# uClouds_002.net
KiCad netlist of a schematic drawn in EAGLE
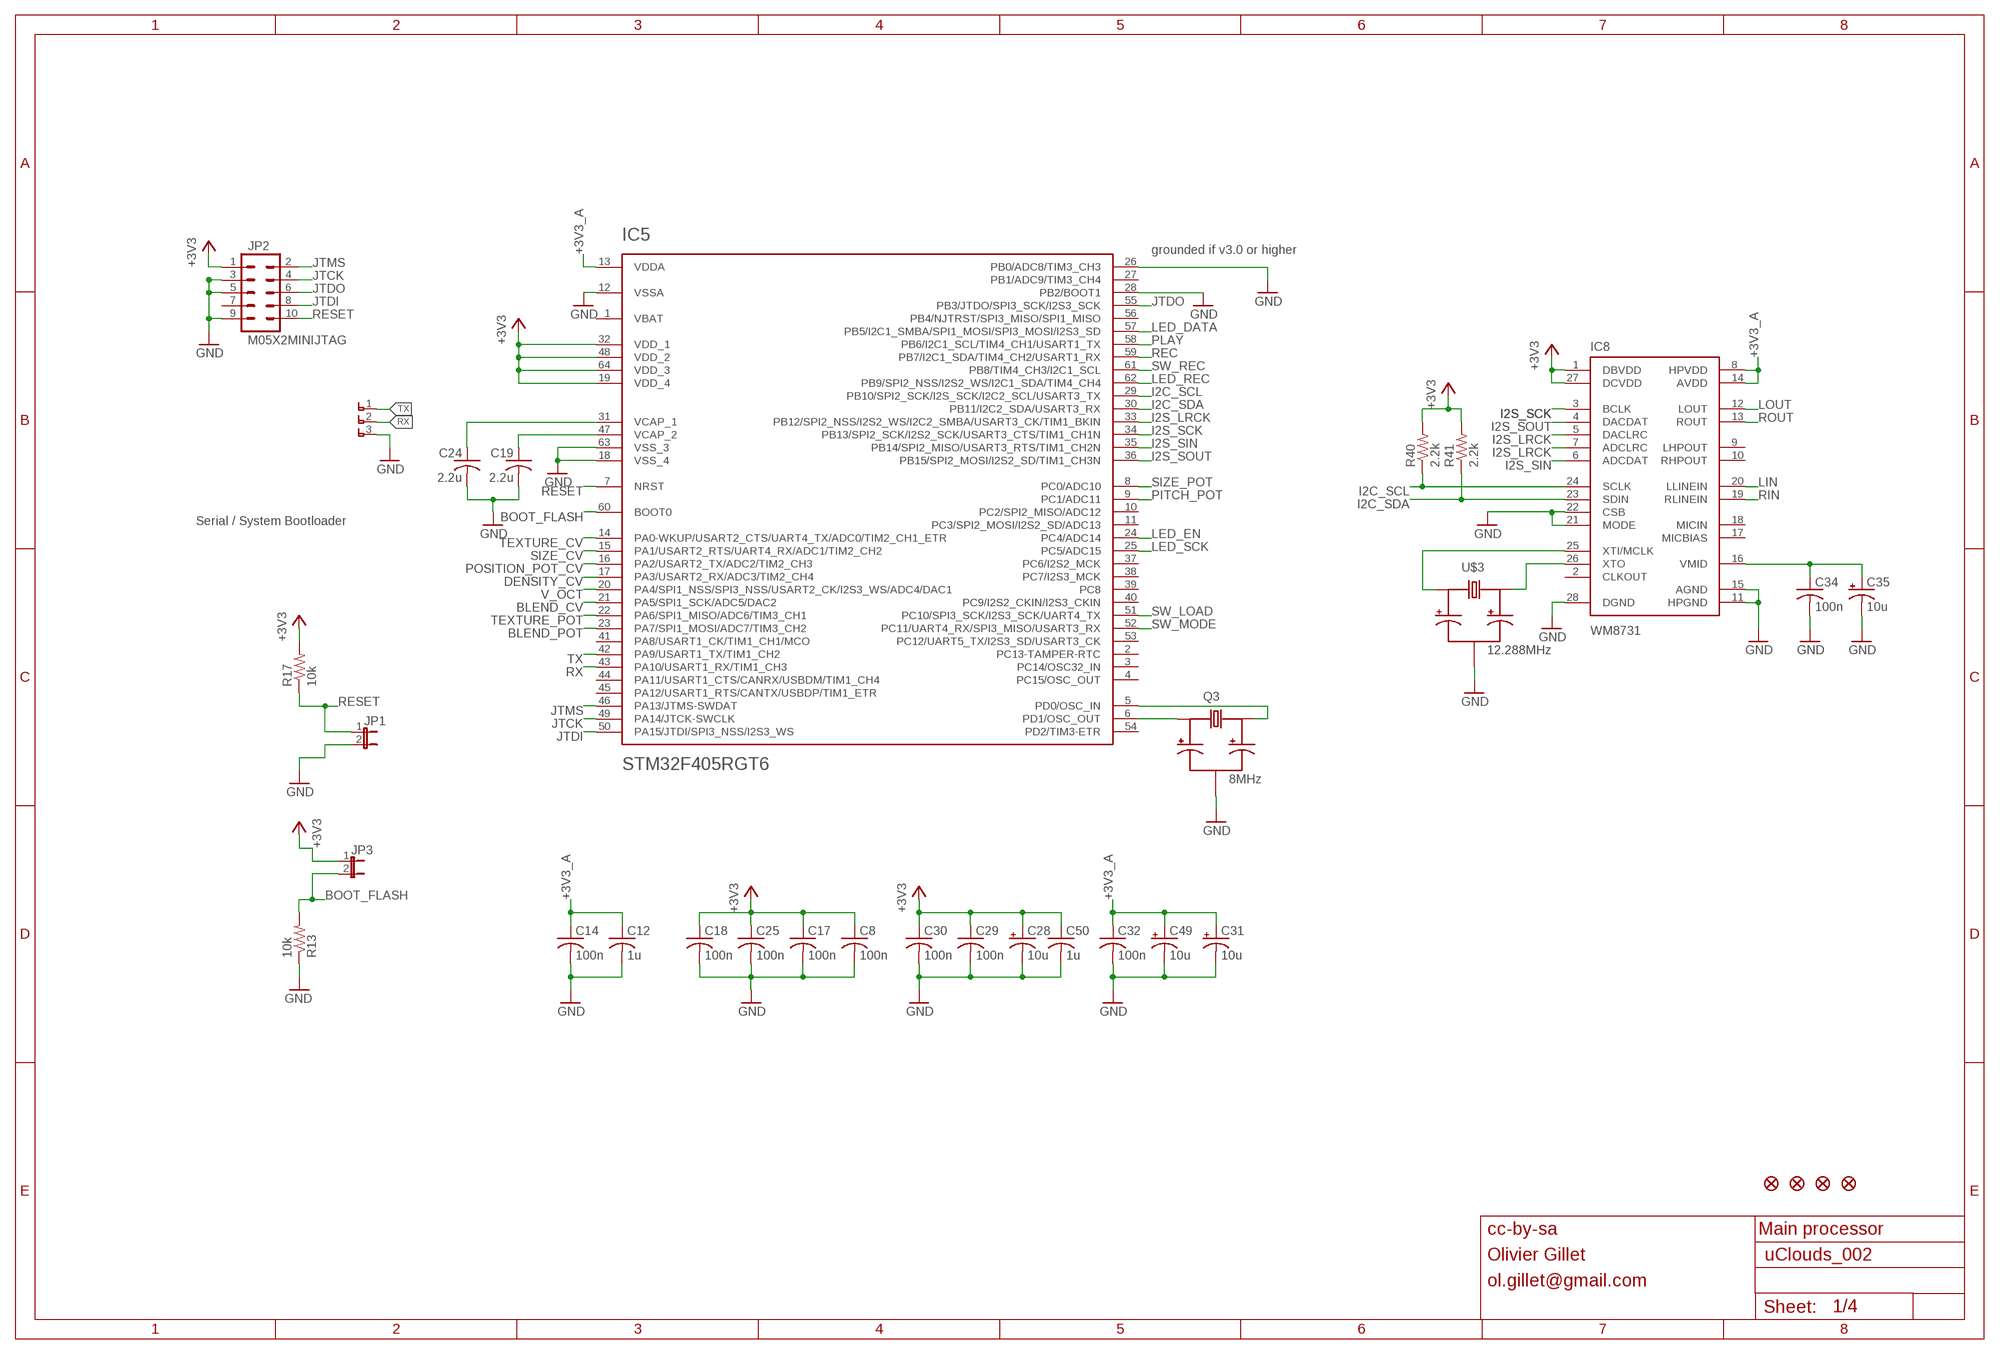
[diagram p0: schematic, sheet 1]
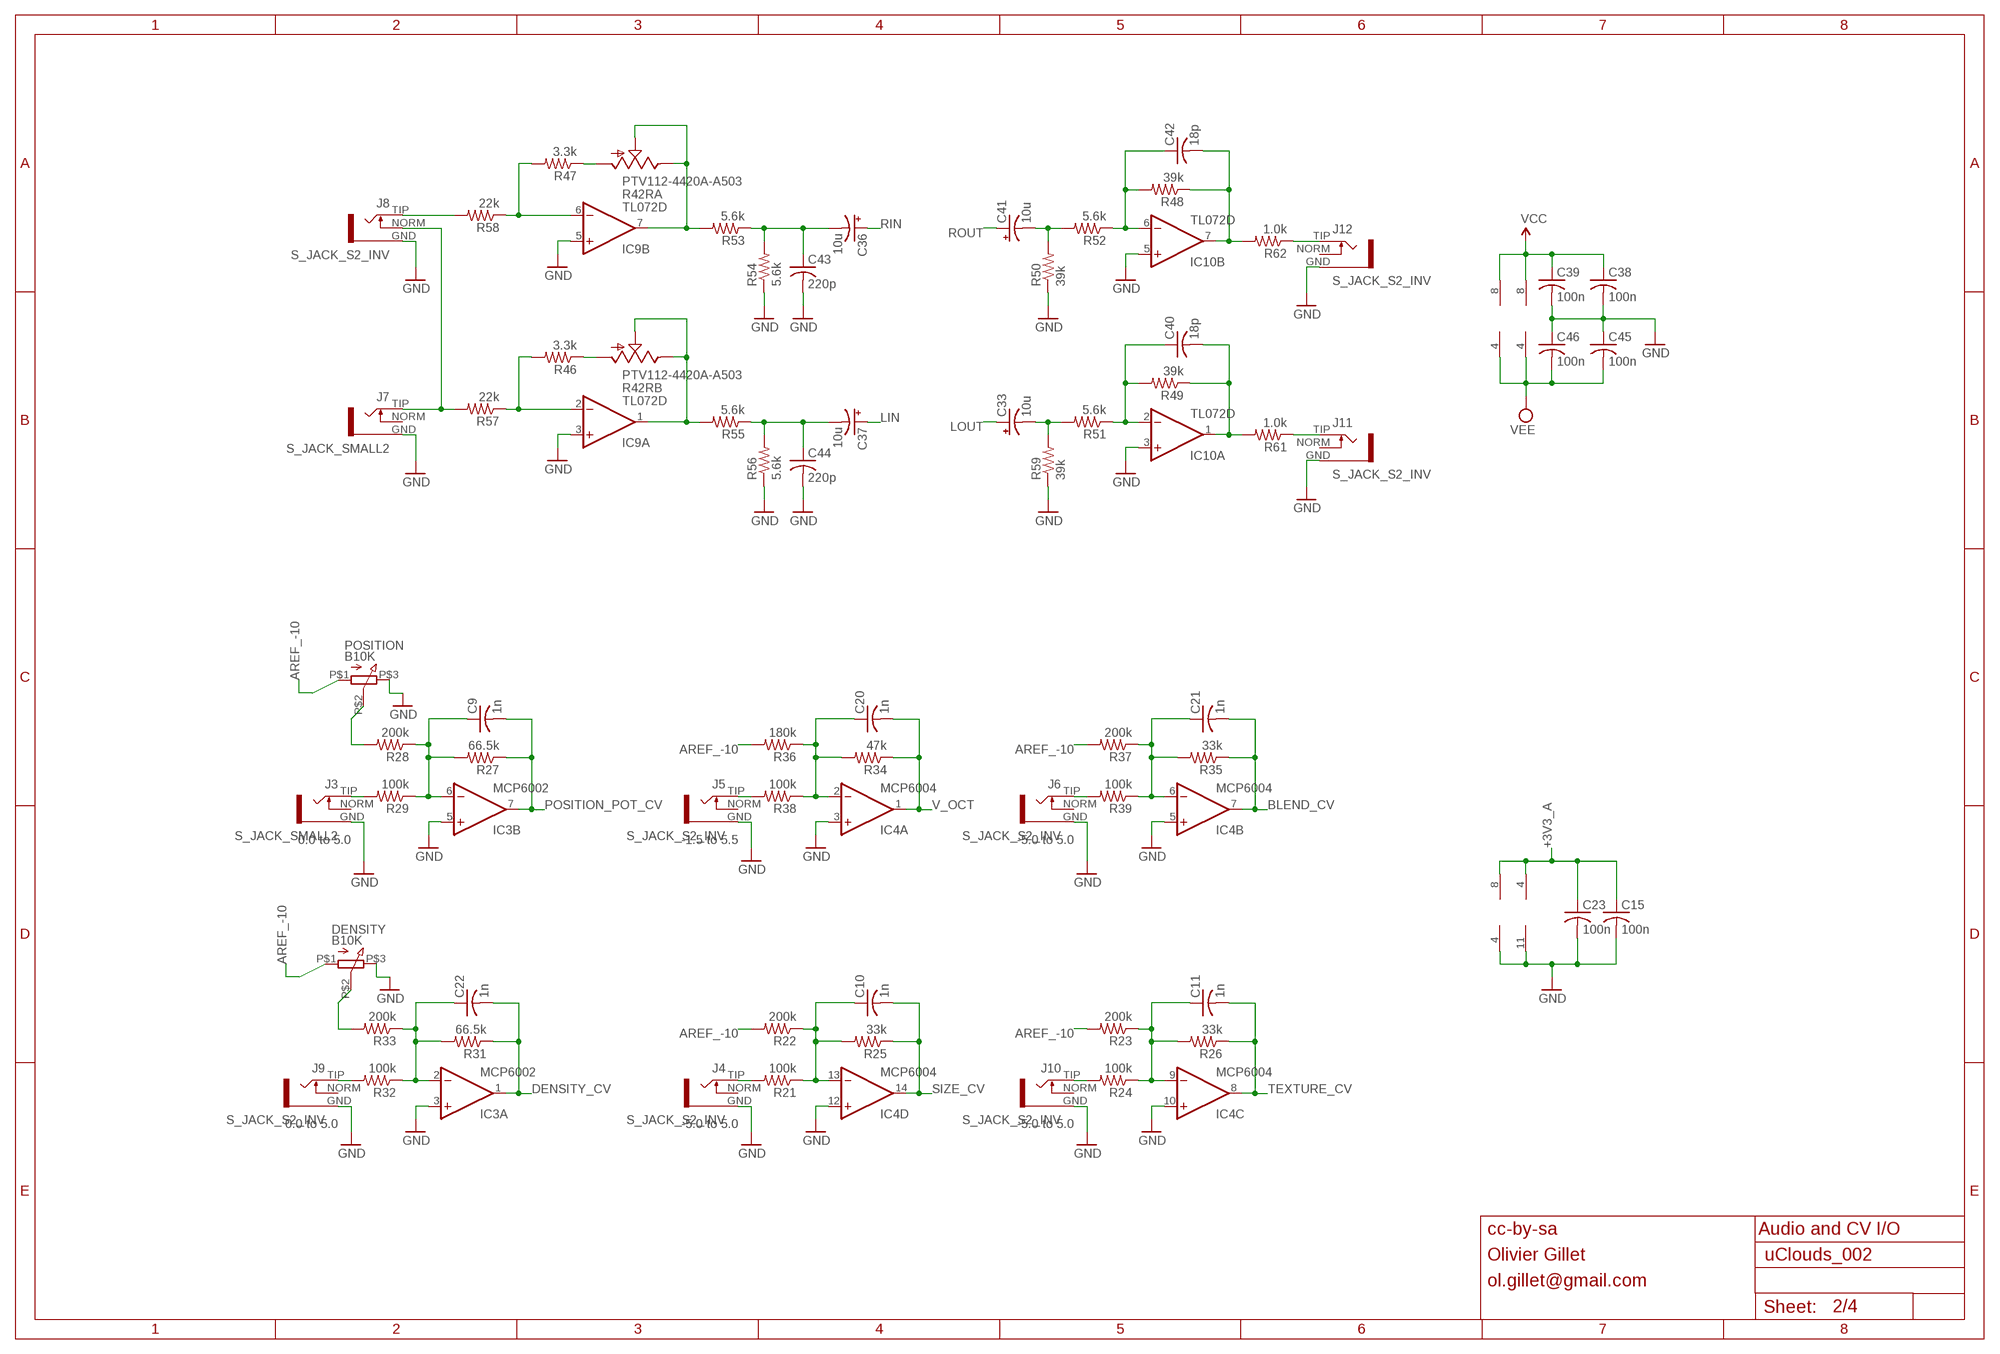
[diagram p1: schematic, sheet 2]
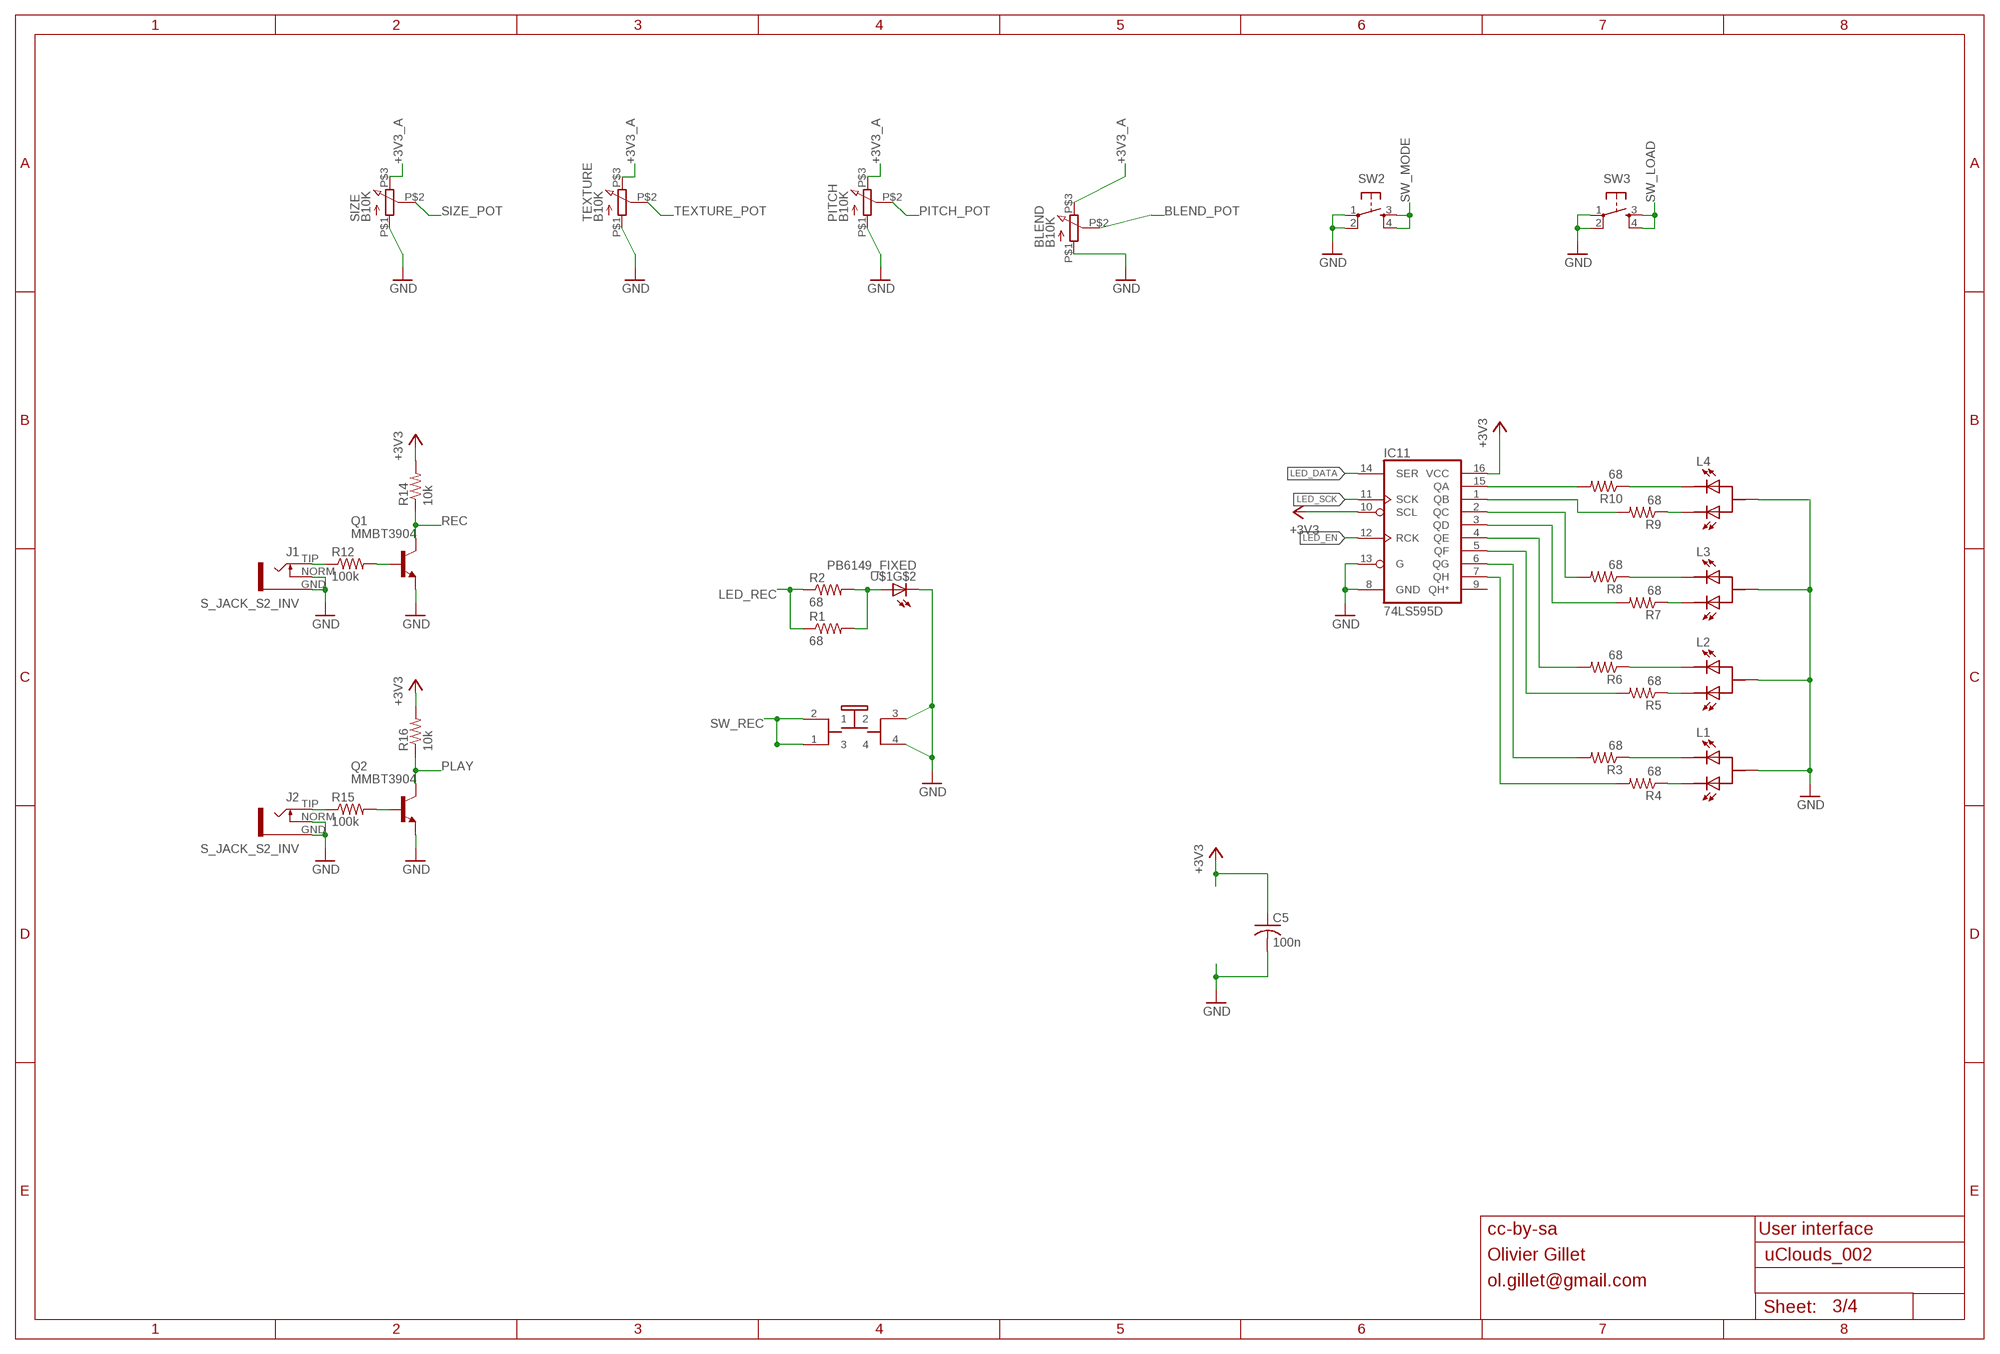
[diagram p2: schematic, sheet 3]
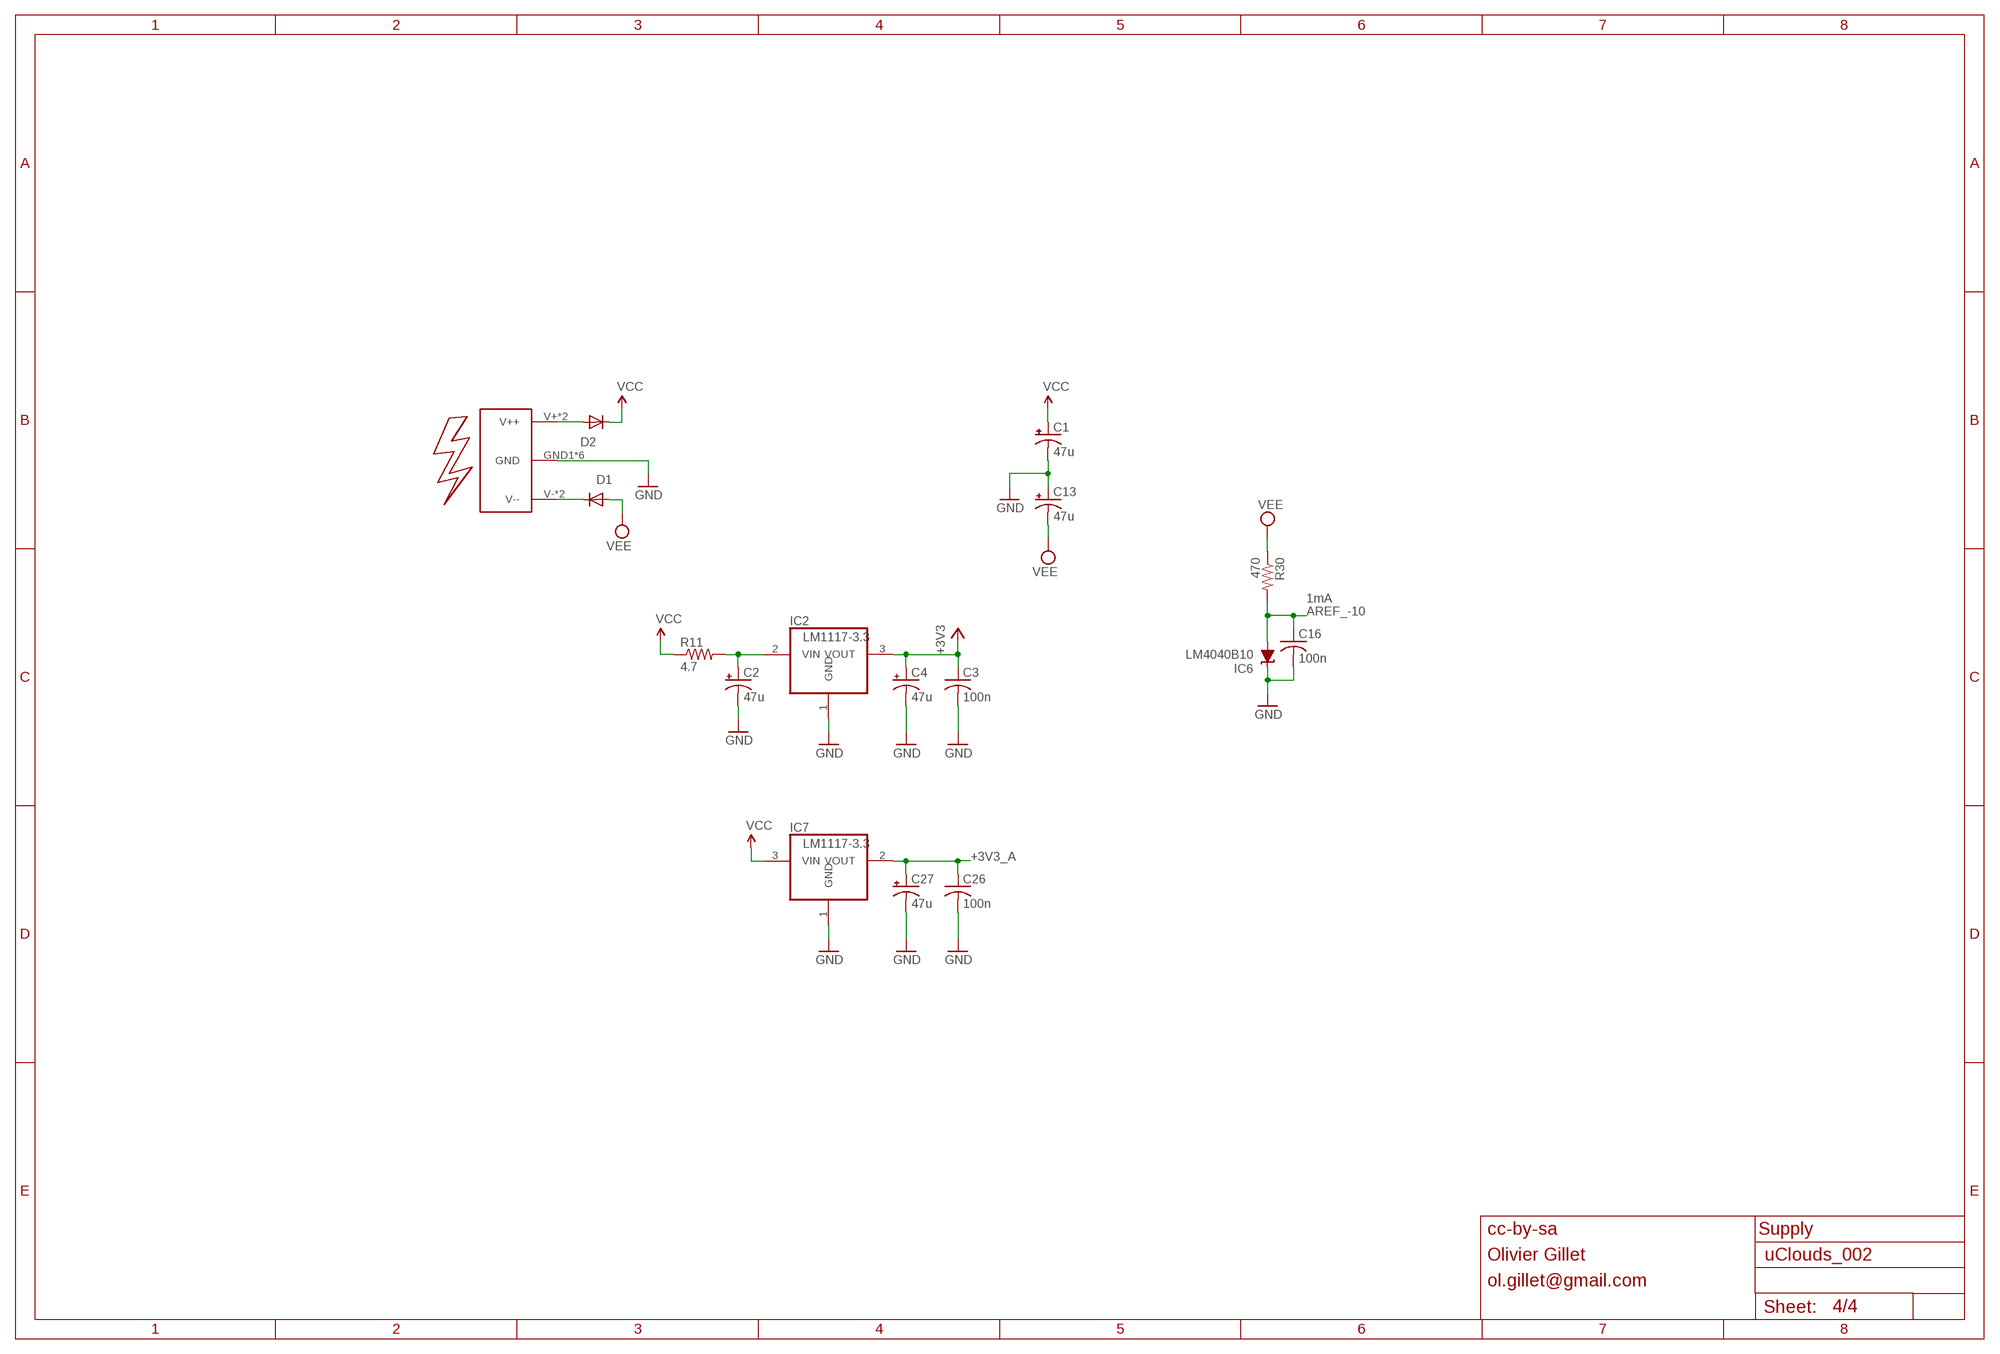
[diagram p3: schematic, sheet 4]

(export (version "E")
  (design (tool "Eeschema 10.0.6"))
  (components
    (comp (ref "C9")
      (value "1n")
      (footprint "eagle-import:C0603")
      (libsource (lib "eagle-import") (part "C-USC0603"))
    )
    (comp (ref "C10")
      (value "1n")
      (footprint "eagle-import:C0603")
      (libsource (lib "eagle-import") (part "C-USC0603"))
    )
    (comp (ref "C11")
      (value "1n")
      (footprint "eagle-import:C0603")
      (libsource (lib "eagle-import") (part "C-USC0603"))
    )
    (comp (ref "C15")
      (value "100n")
      (footprint "eagle-import:C0603K")
      (libsource (lib "eagle-import") (part "rcl@1_C-USC0603K"))
    )
    (comp (ref "C20")
      (value "1n")
      (footprint "eagle-import:C0603")
      (libsource (lib "eagle-import") (part "C-USC0603"))
    )
    (comp (ref "C21")
      (value "1n")
      (footprint "eagle-import:C0603")
      (libsource (lib "eagle-import") (part "C-USC0603"))
    )
    (comp (ref "C22")
      (value "1n")
      (footprint "eagle-import:C0603")
      (libsource (lib "eagle-import") (part "C-USC0603"))
    )
    (comp (ref "C23")
      (value "100n")
      (footprint "eagle-import:C0603")
      (libsource (lib "eagle-import") (part "C-USC0603"))
    )
    (comp (ref "C33")
      (value "10u")
      (footprint "eagle-import:PANASONIC_B")
      (libsource (lib "eagle-import") (part "CPOL-USB"))
    )
    (comp (ref "C36")
      (value "10u")
      (footprint "eagle-import:PANASONIC_B")
      (libsource (lib "eagle-import") (part "CPOL-USB"))
    )
    (comp (ref "C37")
      (value "10u")
      (footprint "eagle-import:PANASONIC_B")
      (libsource (lib "eagle-import") (part "CPOL-USB"))
    )
    (comp (ref "C38")
      (value "100n")
      (footprint "eagle-import:C0603")
      (libsource (lib "eagle-import") (part "C-USC0603"))
    )
    (comp (ref "C39")
      (value "100n")
      (footprint "eagle-import:C0603K")
      (libsource (lib "eagle-import") (part "rcl@1_C-USC0603K"))
    )
    (comp (ref "C40")
      (value "18p")
      (footprint "eagle-import:C0603")
      (libsource (lib "eagle-import") (part "C-USC0603"))
    )
    (comp (ref "C41")
      (value "10u")
      (footprint "eagle-import:PANASONIC_B")
      (libsource (lib "eagle-import") (part "CPOL-USB"))
    )
    (comp (ref "C42")
      (value "18p")
      (footprint "eagle-import:C0603")
      (libsource (lib "eagle-import") (part "C-USC0603"))
    )
    (comp (ref "C43")
      (value "220p")
      (footprint "eagle-import:C0603K")
      (libsource (lib "eagle-import") (part "C-USC0603K"))
    )
    (comp (ref "C44")
      (value "220p")
      (footprint "eagle-import:C0603")
      (libsource (lib "eagle-import") (part "C-USC0603"))
    )
    (comp (ref "C45")
      (value "100n")
      (footprint "eagle-import:C0603")
      (libsource (lib "eagle-import") (part "C-USC0603"))
    )
    (comp (ref "C46")
      (value "100n")
      (footprint "eagle-import:C0603K")
      (libsource (lib "eagle-import") (part "rcl@1_C-USC0603K"))
    )
    (comp (ref "DENSITY")
      (value "B10K")
      (footprint "eagle-import:Q-POT2")
      (libsource (lib "eagle-import") (part "Q-POT2"))
    )
    (comp (ref "IC3")
      (value "MCP6002")
      (footprint "eagle-import:SO08")
      (libsource (lib "eagle-import") (part "TL072D"))
    )
    (comp (ref "IC4")
      (value "MCP6004")
      (footprint "eagle-import:SO14")
      (libsource (lib "eagle-import") (part "TL074D"))
    )
    (comp (ref "IC9")
      (value "TL072D")
      (footprint "eagle-import:SO08")
      (libsource (lib "eagle-import") (part "og-linear_TL072D"))
    )
    (comp (ref "IC10")
      (value "TL072D")
      (footprint "eagle-import:SO08")
      (libsource (lib "eagle-import") (part "og-linear_TL072D"))
    )
    (comp (ref "J3")
      (value "S_JACK_SMALL2")
      (footprint "eagle-import:S_JACK_SMALL2")
      (libsource (lib "eagle-import") (part "S_JACK_SMALL2"))
    )
    (comp (ref "J4")
      (value "S_JACK_S2_INV")
      (footprint "eagle-import:S_JACK_S2_INV")
      (libsource (lib "eagle-import") (part "S_JACK_S2_INV"))
    )
    (comp (ref "J5")
      (value "S_JACK_S2_INV")
      (footprint "eagle-import:S_JACK_S2_INV")
      (libsource (lib "eagle-import") (part "S_JACK_S2_INV"))
    )
    (comp (ref "J6")
      (value "S_JACK_S2_INV")
      (footprint "eagle-import:S_JACK_S2_INV")
      (libsource (lib "eagle-import") (part "S_JACK_S2_INV"))
    )
    (comp (ref "J7")
      (value "S_JACK_SMALL2")
      (footprint "eagle-import:S_JACK_SMALL2")
      (libsource (lib "eagle-import") (part "S_JACK_SMALL2"))
    )
    (comp (ref "J8")
      (value "S_JACK_S2_INV")
      (footprint "eagle-import:S_JACK_S2_INV")
      (libsource (lib "eagle-import") (part "S_JACK_S2_INV"))
    )
    (comp (ref "J9")
      (value "S_JACK_S2_INV")
      (footprint "eagle-import:S_JACK_S2_INV")
      (libsource (lib "eagle-import") (part "S_JACK_S2_INV"))
    )
    (comp (ref "J10")
      (value "S_JACK_S2_INV")
      (footprint "eagle-import:S_JACK_S2_INV")
      (libsource (lib "eagle-import") (part "S_JACK_S2_INV"))
    )
    (comp (ref "J11")
      (value "S_JACK_S2_INV")
      (footprint "eagle-import:S_JACK_S2_INV")
      (libsource (lib "eagle-import") (part "S_JACK_S2_INV"))
    )
    (comp (ref "J12")
      (value "S_JACK_S2_INV")
      (footprint "eagle-import:S_JACK_S2_INV")
      (libsource (lib "eagle-import") (part "S_JACK_S2_INV"))
    )
    (comp (ref "POSITION")
      (value "B10K")
      (footprint "eagle-import:Q-POT2")
      (libsource (lib "eagle-import") (part "Q-POT2"))
    )
    (comp (ref "R21")
      (value "100k")
      (footprint "eagle-import:R0603")
      (libsource (lib "eagle-import") (part "R-US_R0603"))
    )
    (comp (ref "R22")
      (value "200k")
      (footprint "eagle-import:R0603")
      (libsource (lib "eagle-import") (part "R-US_R0603"))
    )
    (comp (ref "R23")
      (value "200k")
      (footprint "eagle-import:R0603")
      (libsource (lib "eagle-import") (part "R-US_R0603"))
    )
    (comp (ref "R24")
      (value "100k")
      (footprint "eagle-import:R0603")
      (libsource (lib "eagle-import") (part "R-US_R0603"))
    )
    (comp (ref "R25")
      (value "33k")
      (footprint "eagle-import:R0603")
      (libsource (lib "eagle-import") (part "R-US_R0603"))
    )
    (comp (ref "R26")
      (value "33k")
      (footprint "eagle-import:R0603")
      (libsource (lib "eagle-import") (part "R-US_R0603"))
    )
    (comp (ref "R27")
      (value "66.5k")
      (footprint "eagle-import:R0603")
      (libsource (lib "eagle-import") (part "R-US_R0603"))
    )
    (comp (ref "R28")
      (value "200k")
      (footprint "eagle-import:R0603")
      (libsource (lib "eagle-import") (part "R-US_R0603"))
    )
    (comp (ref "R29")
      (value "100k")
      (footprint "eagle-import:R0603")
      (libsource (lib "eagle-import") (part "R-US_R0603"))
    )
    (comp (ref "R31")
      (value "66.5k")
      (footprint "eagle-import:R0603")
      (libsource (lib "eagle-import") (part "R-US_R0603"))
    )
    (comp (ref "R32")
      (value "100k")
      (footprint "eagle-import:R0603")
      (libsource (lib "eagle-import") (part "R-US_R0603"))
    )
    (comp (ref "R33")
      (value "200k")
      (footprint "eagle-import:R0603")
      (libsource (lib "eagle-import") (part "R-US_R0603"))
    )
    (comp (ref "R34")
      (value "47k")
      (footprint "eagle-import:R0603")
      (libsource (lib "eagle-import") (part "R-US_R0603"))
    )
    (comp (ref "R35")
      (value "33k")
      (footprint "eagle-import:R0603")
      (libsource (lib "eagle-import") (part "R-US_R0603"))
    )
    (comp (ref "R36")
      (value "180k")
      (footprint "eagle-import:R0603")
      (libsource (lib "eagle-import") (part "R-US_R0603"))
    )
    (comp (ref "R37")
      (value "200k")
      (footprint "eagle-import:R0603")
      (libsource (lib "eagle-import") (part "R-US_R0603"))
    )
    (comp (ref "R38")
      (value "100k")
      (footprint "eagle-import:R0603")
      (libsource (lib "eagle-import") (part "R-US_R0603"))
    )
    (comp (ref "R39")
      (value "100k")
      (footprint "eagle-import:R0603")
      (libsource (lib "eagle-import") (part "R-US_R0603"))
    )
    (comp (ref "R42")
      (value "PTV112-4420A-A503")
      (footprint "eagle-import:BOURNS_PTV112")
      (libsource (lib "eagle-import") (part "POT_US_DUAL_GANG"))
    )
    (comp (ref "R46")
      (value "3.3k")
      (footprint "eagle-import:R0603")
      (libsource (lib "eagle-import") (part "R-US_R0603"))
    )
    (comp (ref "R47")
      (value "3.3k")
      (footprint "eagle-import:R0603")
      (libsource (lib "eagle-import") (part "R-US_R0603"))
    )
    (comp (ref "R48")
      (value "39k")
      (footprint "eagle-import:R0603")
      (libsource (lib "eagle-import") (part "R-US_R0603"))
    )
    (comp (ref "R49")
      (value "39k")
      (footprint "eagle-import:R0603")
      (libsource (lib "eagle-import") (part "R-US_R0603"))
    )
    (comp (ref "R50")
      (value "39k")
      (footprint "eagle-import:R0603")
      (libsource (lib "eagle-import") (part "R-US_R0603"))
    )
    (comp (ref "R51")
      (value "5.6k")
      (footprint "eagle-import:R0603")
      (libsource (lib "eagle-import") (part "R-US_R0603"))
    )
    (comp (ref "R52")
      (value "5.6k")
      (footprint "eagle-import:R0603")
      (libsource (lib "eagle-import") (part "R-US_R0603"))
    )
    (comp (ref "R53")
      (value "5.6k")
      (footprint "eagle-import:R0603")
      (libsource (lib "eagle-import") (part "R-US_R0603"))
    )
    (comp (ref "R54")
      (value "5.6k")
      (footprint "eagle-import:R0603")
      (libsource (lib "eagle-import") (part "R-US_R0603"))
    )
    (comp (ref "R55")
      (value "5.6k")
      (footprint "eagle-import:R0603")
      (libsource (lib "eagle-import") (part "R-US_R0603"))
    )
    (comp (ref "R56")
      (value "5.6k")
      (footprint "eagle-import:R0603")
      (libsource (lib "eagle-import") (part "R-US_R0603"))
    )
    (comp (ref "R57")
      (value "22k")
      (footprint "eagle-import:R0603")
      (libsource (lib "eagle-import") (part "R-US_R0603"))
    )
    (comp (ref "R58")
      (value "22k")
      (footprint "eagle-import:R0603")
      (libsource (lib "eagle-import") (part "R-US_R0603"))
    )
    (comp (ref "R59")
      (value "39k")
      (footprint "eagle-import:R0603")
      (libsource (lib "eagle-import") (part "R-US_R0603"))
    )
    (comp (ref "R61")
      (value "1.0k")
      (footprint "eagle-import:R0603")
      (libsource (lib "eagle-import") (part "R-US_R0603"))
    )
    (comp (ref "R62")
      (value "1.0k")
      (footprint "eagle-import:R0603")
      (libsource (lib "eagle-import") (part "R-US_R0603"))
    )
    (comp (ref "C1")
      (value "47u")
      (footprint "eagle-import:153CLV-0505")
      (libsource (lib "eagle-import") (part "CPOL-US153CLV-0505"))
    )
    (comp (ref "C2")
      (value "47u")
      (footprint "eagle-import:153CLV-0505")
      (libsource (lib "eagle-import") (part "rcl@1_CPOL-US153CLV-0505"))
    )
    (comp (ref "C3")
      (value "100n")
      (footprint "eagle-import:C0603")
      (libsource (lib "eagle-import") (part "C-USC0603"))
    )
    (comp (ref "C4")
      (value "47u")
      (footprint "eagle-import:153CLV-0505")
      (libsource (lib "eagle-import") (part "CPOL-US153CLV-0505"))
    )
    (comp (ref "C13")
      (value "47u")
      (footprint "eagle-import:153CLV-0505")
      (libsource (lib "eagle-import") (part "CPOL-US153CLV-0505"))
    )
    (comp (ref "C16")
      (value "100n")
      (footprint "eagle-import:C0603")
      (libsource (lib "eagle-import") (part "C-USC0603"))
    )
    (comp (ref "C26")
      (value "100n")
      (footprint "eagle-import:C0603")
      (libsource (lib "eagle-import") (part "C-USC0603"))
    )
    (comp (ref "C27")
      (value "47u")
      (footprint "eagle-import:153CLV-0505")
      (libsource (lib "eagle-import") (part "CPOL-US153CLV-0505"))
    )
    (comp (ref "D1")
      (value "1N5819HW")
      (footprint "eagle-import:SOD123")
      (libsource (lib "eagle-import") (part "DIODE-SOD123"))
    )
    (comp (ref "D2")
      (value "1N5819HW")
      (footprint "eagle-import:SOD123")
      (libsource (lib "eagle-import") (part "DIODE-SOD123"))
    )
    (comp (ref "IC2")
      (value "LM1117-3.3")
      (footprint "eagle-import:TO252")
      (libsource (lib "eagle-import") (part "REG1117T"))
    )
    (comp (ref "IC6")
      (value "LM4040B10")
      (footprint "eagle-import:DBZ_R-PDSO-G3")
      (libsource (lib "eagle-import") (part "LM4041DBZB12"))
    )
    (comp (ref "IC7")
      (value "LM1117-3.3")
      (footprint "eagle-import:SOT223")
      (libsource (lib "eagle-import") (part "REG1117"))
    )
    (comp (ref "R11")
      (value "4.7")
      (footprint "eagle-import:R1206")
      (libsource (lib "eagle-import") (part "R-US_R1206"))
    )
    (comp (ref "R30")
      (value "470")
      (footprint "eagle-import:R0603")
      (libsource (lib "eagle-import") (part "R-US_R0603"))
    )
    (comp (ref "U$2")
      (value "EURO_POWER2")
      (footprint "eagle-import:EURO_POWER2")
      (libsource (lib "eagle-import") (part "EURO_POWER2"))
    )
    (comp (ref "C8")
      (value "100n")
      (footprint "eagle-import:C0603")
      (libsource (lib "eagle-import") (part "C-USC0603"))
    )
    (comp (ref "C12")
      (value "1u")
      (footprint "eagle-import:C0603K")
      (libsource (lib "eagle-import") (part "C-USC0603K"))
    )
    (comp (ref "C14")
      (value "100n")
      (footprint "eagle-import:C0603K")
      (libsource (lib "eagle-import") (part "C-USC0603K"))
    )
    (comp (ref "C17")
      (value "100n")
      (footprint "eagle-import:C0603K")
      (libsource (lib "eagle-import") (part "C-USC0603K"))
    )
    (comp (ref "C18")
      (value "100n")
      (footprint "eagle-import:C0603K")
      (libsource (lib "eagle-import") (part "C-USC0603K"))
    )
    (comp (ref "C19")
      (value "2.2u")
      (footprint "eagle-import:C0805K")
      (libsource (lib "eagle-import") (part "rcl@1_C-USC0805K"))
    )
    (comp (ref "C24")
      (value "2.2u")
      (footprint "eagle-import:C0805K")
      (libsource (lib "eagle-import") (part "rcl@1_C-USC0805K"))
    )
    (comp (ref "C25")
      (value "100n")
      (footprint "eagle-import:C0603K")
      (libsource (lib "eagle-import") (part "rcl@1_C-USC0603K"))
    )
    (comp (ref "C28")
      (value "10u")
      (footprint "eagle-import:153CLV-0405")
      (libsource (lib "eagle-import") (part "rcl@1_CPOL-US153CLV-0405"))
    )
    (comp (ref "C29")
      (value "100n")
      (footprint "eagle-import:C0603K")
      (libsource (lib "eagle-import") (part "C-USC0603K"))
    )
    (comp (ref "C30")
      (value "100n")
      (footprint "eagle-import:C0603K")
      (libsource (lib "eagle-import") (part "rcl@1_C-USC0603K"))
    )
    (comp (ref "C31")
      (value "10u")
      (footprint "eagle-import:PANASONIC_B")
      (libsource (lib "eagle-import") (part "CPOL-USB"))
    )
    (comp (ref "C32")
      (value "100n")
      (footprint "eagle-import:C0603")
      (libsource (lib "eagle-import") (part "C-USC0603"))
    )
    (comp (ref "C34")
      (value "100n")
      (footprint "eagle-import:C0603")
      (libsource (lib "eagle-import") (part "C-USC0603"))
    )
    (comp (ref "C35")
      (value "10u")
      (footprint "eagle-import:PANASONIC_B")
      (libsource (lib "eagle-import") (part "CPOL-USB"))
    )
    (comp (ref "C49")
      (value "10u")
      (footprint "eagle-import:PANASONIC_A")
      (libsource (lib "eagle-import") (part "CPOL-USA"))
    )
    (comp (ref "C50")
      (value "1u")
      (footprint "eagle-import:C0603K")
      (libsource (lib "eagle-import") (part "rcl@1_C-USC0603K"))
    )
    (comp (ref "F1")
      (value "FIDUCIAL1X2")
      (footprint "eagle-import:FIDUCIAL-1X2")
      (libsource (lib "eagle-import") (part "FIDUCIAL1X2"))
    )
    (comp (ref "F2")
      (value "FIDUCIAL1X2")
      (footprint "eagle-import:FIDUCIAL-1X2")
      (libsource (lib "eagle-import") (part "FIDUCIAL1X2"))
    )
    (comp (ref "F3")
      (value "FIDUCIAL1X2")
      (footprint "eagle-import:FIDUCIAL-1X2")
      (libsource (lib "eagle-import") (part "FIDUCIAL1X2"))
    )
    (comp (ref "F4")
      (value "FIDUCIAL1X2")
      (footprint "eagle-import:FIDUCIAL-1X2")
      (libsource (lib "eagle-import") (part "FIDUCIAL1X2"))
    )
    (comp (ref "IC5")
      (value "STM32F405RGT6")
      (footprint "eagle-import:TQFP-10X10-64")
      (libsource (lib "eagle-import") (part "STM32F20X"))
    )
    (comp (ref "IC8")
      (value "WM8731")
      (footprint "eagle-import:SSOP28")
      (libsource (lib "eagle-import") (part "WM8731"))
    )
    (comp (ref "JP1")
      (value "JUMPER-2SMD-NO")
      (footprint "eagle-import:SJ_2S-NO")
      (libsource (lib "eagle-import") (part "JUMPER-2SMD-NO"))
    )
    (comp (ref "JP2")
      (value "M05X2MINIJTAG")
      (footprint "eagle-import:2X5-1.27")
      (libsource (lib "eagle-import") (part "M05X2MINIJTAG"))
    )
    (comp (ref "JP3")
      (value "JUMPER-2SMD-NO")
      (footprint "eagle-import:SJ_2S-NO")
      (libsource (lib "eagle-import") (part "JUMPER-2SMD-NO"))
    )
    (comp (ref "Q3")
      (value "8MHz")
      (footprint "eagle-import:CRYSTAL_SMALLER")
      (libsource (lib "eagle-import") (part "CRYSTAL_SMALLER"))
    )
    (comp (ref "R13")
      (value "10k")
      (footprint "eagle-import:R0603")
      (libsource (lib "eagle-import") (part "R-US_R0603"))
    )
    (comp (ref "R17")
      (value "10k")
      (footprint "eagle-import:R0603")
      (libsource (lib "eagle-import") (part "R-US_R0603"))
    )
    (comp (ref "R40")
      (value "2.2k")
      (footprint "eagle-import:R0603")
      (libsource (lib "eagle-import") (part "R-US_R0603"))
    )
    (comp (ref "R41")
      (value "2.2k")
      (footprint "eagle-import:R0603")
      (libsource (lib "eagle-import") (part "R-US_R0603"))
    )
    (comp (ref "U$3")
      (value "12.288MHz")
      (footprint "eagle-import:CRYSTAL_SMALLER")
      (libsource (lib "eagle-import") (part "CRYSTAL_SMALLER"))
    )
    (comp (ref "U$4")
      (value "1X3_SMALL")
      (footprint "eagle-import:1X3_SMALL")
      (libsource (lib "eagle-import") (part "1X3_SMALL"))
    )
    (comp (ref "BLEND")
      (value "B10K")
      (footprint "eagle-import:Q-POT2")
      (libsource (lib "eagle-import") (part "Q-POT2"))
    )
    (comp (ref "C5")
      (value "100n")
      (footprint "eagle-import:C0603")
      (libsource (lib "eagle-import") (part "C-USC0603"))
    )
    (comp (ref "IC11")
      (value "74LS595D")
      (footprint "eagle-import:SO16")
      (libsource (lib "eagle-import") (part "74595DLS"))
    )
    (comp (ref "J1")
      (value "S_JACK_S2_INV")
      (footprint "eagle-import:S_JACK_S2_INV")
      (libsource (lib "eagle-import") (part "S_JACK_S2_INV"))
    )
    (comp (ref "J2")
      (value "S_JACK_S2_INV")
      (footprint "eagle-import:S_JACK_S2_INV")
      (libsource (lib "eagle-import") (part "S_JACK_S2_INV"))
    )
    (comp (ref "L1")
      (value "LED_3MM_3PIN")
      (footprint "eagle-import:LED_3MM_3PIN")
      (libsource (lib "eagle-import") (part "LED_3MM_3PIN"))
    )
    (comp (ref "L2")
      (value "LED_3MM_3PIN")
      (footprint "eagle-import:LED_3MM_3PIN")
      (libsource (lib "eagle-import") (part "LED_3MM_3PIN"))
    )
    (comp (ref "L3")
      (value "LED_3MM_3PIN")
      (footprint "eagle-import:LED_3MM_3PIN")
      (libsource (lib "eagle-import") (part "LED_3MM_3PIN"))
    )
    (comp (ref "L4")
      (value "LED_3MM_3PIN")
      (footprint "eagle-import:LED_3MM_3PIN")
      (libsource (lib "eagle-import") (part "LED_3MM_3PIN"))
    )
    (comp (ref "PITCH")
      (value "B10K")
      (footprint "eagle-import:Q-POT2")
      (libsource (lib "eagle-import") (part "Q-POT2"))
    )
    (comp (ref "Q1")
      (value "MMBT3904")
      (footprint "eagle-import:SOT23-BEC")
      (libsource (lib "eagle-import") (part "-NPN-SOT23-BECMMBT3904LT1"))
    )
    (comp (ref "Q2")
      (value "MMBT3904")
      (footprint "eagle-import:SOT23-BEC")
      (libsource (lib "eagle-import") (part "-NPN-SOT23-BECMMBT3904LT1"))
    )
    (comp (ref "R1")
      (value "68")
      (footprint "eagle-import:R0603")
      (libsource (lib "eagle-import") (part "R-US_R0603"))
    )
    (comp (ref "R2")
      (value "68")
      (footprint "eagle-import:R0603")
      (libsource (lib "eagle-import") (part "R-US_R0603"))
    )
    (comp (ref "R3")
      (value "68")
      (footprint "eagle-import:R0603")
      (libsource (lib "eagle-import") (part "R-US_R0603"))
    )
    (comp (ref "R4")
      (value "68")
      (footprint "eagle-import:R0603")
      (libsource (lib "eagle-import") (part "R-US_R0603"))
    )
    (comp (ref "R5")
      (value "68")
      (footprint "eagle-import:R0603")
      (libsource (lib "eagle-import") (part "R-US_R0603"))
    )
    (comp (ref "R6")
      (value "68")
      (footprint "eagle-import:R0603")
      (libsource (lib "eagle-import") (part "R-US_R0603"))
    )
    (comp (ref "R7")
      (value "68")
      (footprint "eagle-import:R0603")
      (libsource (lib "eagle-import") (part "R-US_R0603"))
    )
    (comp (ref "R8")
      (value "68")
      (footprint "eagle-import:R0603")
      (libsource (lib "eagle-import") (part "R-US_R0603"))
    )
    (comp (ref "R9")
      (value "68")
      (footprint "eagle-import:R0603")
      (libsource (lib "eagle-import") (part "R-US_R0603"))
    )
    (comp (ref "R10")
      (value "68")
      (footprint "eagle-import:R0603")
      (libsource (lib "eagle-import") (part "R-US_R0603"))
    )
    (comp (ref "R12")
      (value "100k")
      (footprint "eagle-import:R0603")
      (libsource (lib "eagle-import") (part "R-US_R0603"))
    )
    (comp (ref "R14")
      (value "10k")
      (footprint "eagle-import:R0603")
      (libsource (lib "eagle-import") (part "R-US_R0603"))
    )
    (comp (ref "R15")
      (value "100k")
      (footprint "eagle-import:R0603")
      (libsource (lib "eagle-import") (part "R-US_R0603"))
    )
    (comp (ref "R16")
      (value "10k")
      (footprint "eagle-import:R0603")
      (libsource (lib "eagle-import") (part "R-US_R0603"))
    )
    (comp (ref "SIZE")
      (value "B10K")
      (footprint "eagle-import:Q-POT2")
      (libsource (lib "eagle-import") (part "Q-POT2"))
    )
    (comp (ref "SW2")
      (value "TAC_SWITCHPTH")
      (footprint "eagle-import:TACTILE-PTH")
      (libsource (lib "eagle-import") (part "TAC_SWITCHPTH"))
    )
    (comp (ref "SW3")
      (value "TAC_SWITCHPTH")
      (footprint "eagle-import:TACTILE-PTH")
      (libsource (lib "eagle-import") (part "TAC_SWITCHPTH"))
    )
    (comp (ref "TEXTURE")
      (value "B10K")
      (footprint "eagle-import:Q-POT2")
      (libsource (lib "eagle-import") (part "Q-POT2"))
    )
    (comp (ref "U$1")
      (value "PB6149_FIXED")
      (footprint "eagle-import:PB6149L")
      (libsource (lib "eagle-import") (part "PB6149_FIXED"))
    )
  )
  (nets
    (net (code "1") (name "+3V3") (class "Default")
      (node (ref "C17") (pin "1") (pinfunction "1_1") (pintype "passive"))
      (node (ref "C18") (pin "1") (pinfunction "1_1") (pintype "passive"))
      (node (ref "C25") (pin "1") (pinfunction "1_1") (pintype "passive"))
      (node (ref "C28") (pin "+") (pinfunction "+_+") (pintype "passive"))
      (node (ref "C29") (pin "1") (pinfunction "1_1") (pintype "passive"))
      (node (ref "C3") (pin "1") (pinfunction "1_1") (pintype "passive"))
      (node (ref "C30") (pin "1") (pinfunction "1_1") (pintype "passive"))
      (node (ref "C4") (pin "+") (pinfunction "+_+") (pintype "passive"))
      (node (ref "C5") (pin "1") (pinfunction "1_1") (pintype "passive"))
      (node (ref "C50") (pin "1") (pinfunction "1_1") (pintype "passive"))
      (node (ref "C8") (pin "1") (pinfunction "1_1") (pintype "passive"))
      (node (ref "IC11") (pin "10") (pinfunction "SCL_10") (pintype "input"))
      (node (ref "IC11") (pin "16") (pinfunction "VCC_16") (pintype "power_in"))
      (node (ref "IC2") (pin "3") (pinfunction "VOUT_3") (pintype "output"))
      (node (ref "IC5") (pin "19") (pinfunction "VDD_4_19") (pintype "power_in"))
      (node (ref "IC5") (pin "32") (pinfunction "VDD_1_32") (pintype "power_in"))
      (node (ref "IC5") (pin "48") (pinfunction "VDD_2_48") (pintype "power_in"))
      (node (ref "IC5") (pin "64") (pinfunction "VDD_3_64") (pintype "power_in"))
      (node (ref "IC8") (pin "1") (pinfunction "DBVDD_1") (pintype "bidirectional"))
      (node (ref "IC8") (pin "27") (pinfunction "DCVDD_27") (pintype "bidirectional"))
      (node (ref "JP2") (pin "1") (pinfunction "1_1") (pintype "passive"))
      (node (ref "JP3") (pin "1") (pinfunction "1_1") (pintype "passive"))
      (node (ref "R14") (pin "2") (pinfunction "2_2") (pintype "passive"))
      (node (ref "R16") (pin "2") (pinfunction "2_2") (pintype "passive"))
      (node (ref "R17") (pin "2") (pinfunction "2_2") (pintype "passive"))
      (node (ref "R40") (pin "2") (pinfunction "2_2") (pintype "passive"))
      (node (ref "R41") (pin "2") (pinfunction "2_2") (pintype "passive"))
    )
    (net (code "2") (name "+3V3_A") (class "Default")
      (node (ref "BLEND") (pin "P$3") (pinfunction "3_P$3") (pintype "passive"))
      (node (ref "C12") (pin "1") (pinfunction "1_1") (pintype "passive"))
      (node (ref "C14") (pin "1") (pinfunction "1_1") (pintype "passive"))
      (node (ref "C15") (pin "1") (pinfunction "1_1") (pintype "passive"))
      (node (ref "C23") (pin "1") (pinfunction "1_1") (pintype "passive"))
      (node (ref "C26") (pin "1") (pinfunction "1_1") (pintype "passive"))
      (node (ref "C27") (pin "+") (pinfunction "+_+") (pintype "passive"))
      (node (ref "C31") (pin "+") (pinfunction "+_+") (pintype "passive"))
      (node (ref "C32") (pin "1") (pinfunction "1_1") (pintype "passive"))
      (node (ref "C49") (pin "+") (pinfunction "+_+") (pintype "passive"))
      (node (ref "IC3") (pin "8") (pinfunction "V+_8") (pintype "power_in"))
      (node (ref "IC4") (pin "4") (pinfunction "V+_4") (pintype "power_in"))
      (node (ref "IC5") (pin "13") (pinfunction "VDDA_13") (pintype "power_in"))
      (node (ref "IC7") (pin "2") (pinfunction "VOUT_2") (pintype "output"))
      (node (ref "IC8") (pin "14") (pinfunction "AVDD_14") (pintype "bidirectional"))
      (node (ref "IC8") (pin "8") (pinfunction "HPVDD_8") (pintype "bidirectional"))
      (node (ref "PITCH") (pin "P$3") (pinfunction "3_P$3") (pintype "passive"))
      (node (ref "SIZE") (pin "P$3") (pinfunction "3_P$3") (pintype "passive"))
      (node (ref "TEXTURE") (pin "P$3") (pinfunction "3_P$3") (pintype "passive"))
    )
    (net (code "3") (name "AREF_-10") (class "Default")
      (node (ref "C16") (pin "1") (pinfunction "1_1") (pintype "passive"))
      (node (ref "DENSITY") (pin "P$1") (pinfunction "1_P$1") (pintype "passive"))
      (node (ref "IC6") (pin "2") (pinfunction "A_2") (pintype "passive"))
      (node (ref "POSITION") (pin "P$1") (pinfunction "1_P$1") (pintype "passive"))
      (node (ref "R22") (pin "2") (pinfunction "2_2") (pintype "passive"))
      (node (ref "R23") (pin "2") (pinfunction "2_2") (pintype "passive"))
      (node (ref "R30") (pin "2") (pinfunction "2_2") (pintype "passive"))
      (node (ref "R36") (pin "2") (pinfunction "2_2") (pintype "passive"))
      (node (ref "R37") (pin "2") (pinfunction "2_2") (pintype "passive"))
    )
    (net (code "4") (name "BLEND_CV") (class "Default")
      (node (ref "C21") (pin "2") (pinfunction "2_2") (pintype "passive"))
      (node (ref "IC4") (pin "7") (pinfunction "OUT_7") (pintype "output"))
      (node (ref "IC5") (pin "21") (pinfunction "PA5/SPI1_SCK/ADC5/DAC2_21") (pintype "bidirectional"))
      (node (ref "R35") (pin "1") (pinfunction "1_1") (pintype "passive"))
    )
    (net (code "5") (name "BLEND_POT") (class "Default")
      (node (ref "BLEND") (pin "P$2") (pinfunction "2_P$2") (pintype "passive"))
      (node (ref "IC5") (pin "23") (pinfunction "PA7/SPI1_MOSI/ADC7/TIM3_CH2_23") (pintype "bidirectional"))
    )
    (net (code "6") (name "BOOT_FLASH") (class "Default")
      (node (ref "IC5") (pin "60") (pinfunction "BOOT0_60") (pintype "bidirectional"))
      (node (ref "JP3") (pin "2") (pinfunction "2_2") (pintype "passive"))
      (node (ref "R13") (pin "2") (pinfunction "2_2") (pintype "passive"))
    )
    (net (code "7") (name "DENSITY_CV") (class "Default")
      (node (ref "C22") (pin "2") (pinfunction "2_2") (pintype "passive"))
      (node (ref "IC3") (pin "1") (pinfunction "OUT_1") (pintype "output"))
      (node (ref "IC5") (pin "17") (pinfunction "PA3/USART2_RX/ADC3/TIM2_CH4_17") (pintype "bidirectional"))
      (node (ref "R31") (pin "1") (pinfunction "1_1") (pintype "passive"))
    )
    (net (code "8") (name "GND") (class "Default")
      (node (ref "BLEND") (pin "P$1") (pinfunction "1_P$1") (pintype "passive"))
      (node (ref "C1") (pin "-") (pinfunction "-_-") (pintype "passive"))
      (node (ref "C12") (pin "2") (pinfunction "2_2") (pintype "passive"))
      (node (ref "C13") (pin "+") (pinfunction "+_+") (pintype "passive"))
      (node (ref "C14") (pin "2") (pinfunction "2_2") (pintype "passive"))
      (node (ref "C15") (pin "2") (pinfunction "2_2") (pintype "passive"))
      (node (ref "C16") (pin "2") (pinfunction "2_2") (pintype "passive"))
      (node (ref "C17") (pin "2") (pinfunction "2_2") (pintype "passive"))
      (node (ref "C18") (pin "2") (pinfunction "2_2") (pintype "passive"))
      (node (ref "C19") (pin "2") (pinfunction "2_2") (pintype "passive"))
      (node (ref "C2") (pin "-") (pinfunction "-_-") (pintype "passive"))
      (node (ref "C23") (pin "2") (pinfunction "2_2") (pintype "passive"))
      (node (ref "C24") (pin "2") (pinfunction "2_2") (pintype "passive"))
      (node (ref "C25") (pin "2") (pinfunction "2_2") (pintype "passive"))
      (node (ref "C26") (pin "2") (pinfunction "2_2") (pintype "passive"))
      (node (ref "C27") (pin "-") (pinfunction "-_-") (pintype "passive"))
      (node (ref "C28") (pin "-") (pinfunction "-_-") (pintype "passive"))
      (node (ref "C29") (pin "2") (pinfunction "2_2") (pintype "passive"))
      (node (ref "C3") (pin "2") (pinfunction "2_2") (pintype "passive"))
      (node (ref "C30") (pin "2") (pinfunction "2_2") (pintype "passive"))
      (node (ref "C31") (pin "-") (pinfunction "-_-") (pintype "passive"))
      (node (ref "C32") (pin "2") (pinfunction "2_2") (pintype "passive"))
      (node (ref "C34") (pin "2") (pinfunction "2_2") (pintype "passive"))
      (node (ref "C35") (pin "-") (pinfunction "-_-") (pintype "passive"))
      (node (ref "C38") (pin "2") (pinfunction "2_2") (pintype "passive"))
      (node (ref "C39") (pin "2") (pinfunction "2_2") (pintype "passive"))
      (node (ref "C4") (pin "-") (pinfunction "-_-") (pintype "passive"))
      (node (ref "C43") (pin "2") (pinfunction "2_2") (pintype "passive"))
      (node (ref "C44") (pin "2") (pinfunction "2_2") (pintype "passive"))
      (node (ref "C45") (pin "1") (pinfunction "1_1") (pintype "passive"))
      (node (ref "C46") (pin "1") (pinfunction "1_1") (pintype "passive"))
      (node (ref "C49") (pin "-") (pinfunction "-_-") (pintype "passive"))
      (node (ref "C5") (pin "2") (pinfunction "2_2") (pintype "passive"))
      (node (ref "C50") (pin "2") (pinfunction "2_2") (pintype "passive"))
      (node (ref "C8") (pin "2") (pinfunction "2_2") (pintype "passive"))
      (node (ref "DENSITY") (pin "P$3") (pinfunction "3_P$3") (pintype "passive"))
      (node (ref "IC10") (pin "3") (pinfunction "+IN_3") (pintype "input"))
      (node (ref "IC10") (pin "5") (pinfunction "+IN_5") (pintype "input"))
      (node (ref "IC11") (pin "13") (pinfunction "G_13") (pintype "input"))
      (node (ref "IC11") (pin "8") (pinfunction "GND_8") (pintype "power_in"))
      (node (ref "IC2") (pin "1") (pinfunction "GND_1") (pintype "power_in"))
      (node (ref "IC3") (pin "3") (pinfunction "+IN_3") (pintype "input"))
      (node (ref "IC3") (pin "4") (pinfunction "V-_4") (pintype "power_in"))
      (node (ref "IC3") (pin "5") (pinfunction "+IN_5") (pintype "input"))
      (node (ref "IC4") (pin "10") (pinfunction "+IN_10") (pintype "input"))
      (node (ref "IC4") (pin "11") (pinfunction "V-_11") (pintype "power_in"))
      (node (ref "IC4") (pin "12") (pinfunction "+IN_12") (pintype "input"))
      (node (ref "IC4") (pin "3") (pinfunction "+IN_3") (pintype "input"))
      (node (ref "IC4") (pin "5") (pinfunction "+IN_5") (pintype "input"))
      (node (ref "IC5") (pin "12") (pinfunction "VSSA_12") (pintype "power_in"))
      (node (ref "IC5") (pin "18") (pinfunction "VSS_4_18") (pintype "power_in"))
      (node (ref "IC5") (pin "26") (pinfunction "PB0/ADC8/TIM3_CH3_26") (pintype "bidirectional"))
      (node (ref "IC5") (pin "28") (pinfunction "PB2/BOOT1_28") (pintype "bidirectional"))
      (node (ref "IC5") (pin "63") (pinfunction "VSS_3_63") (pintype "power_in"))
      (node (ref "IC6") (pin "1") (pinfunction "C_1") (pintype "passive"))
      (node (ref "IC7") (pin "1") (pinfunction "GND_1") (pintype "power_in"))
      (node (ref "IC8") (pin "11") (pinfunction "HPGND_11") (pintype "bidirectional"))
      (node (ref "IC8") (pin "15") (pinfunction "AGND_15") (pintype "bidirectional"))
      (node (ref "IC8") (pin "21") (pinfunction "MODE_21") (pintype "bidirectional"))
      (node (ref "IC8") (pin "22") (pinfunction "CSB_22") (pintype "bidirectional"))
      (node (ref "IC8") (pin "28") (pinfunction "DGND_28") (pintype "bidirectional"))
      (node (ref "IC9") (pin "3") (pinfunction "+IN_3") (pintype "input"))
      (node (ref "IC9") (pin "5") (pinfunction "+IN_5") (pintype "input"))
      (node (ref "J1") (pin "GND") (pinfunction "GND_GND") (pintype "passive"))
      (node (ref "J1") (pin "NORM") (pinfunction "NORM_NORM") (pintype "passive"))
      (node (ref "J10") (pin "GND") (pinfunction "GND_GND") (pintype "passive"))
      (node (ref "J11") (pin "GND") (pinfunction "GND_GND") (pintype "passive"))
      (node (ref "J12") (pin "GND") (pinfunction "GND_GND") (pintype "passive"))
      (node (ref "J2") (pin "GND") (pinfunction "GND_GND") (pintype "passive"))
      (node (ref "J2") (pin "NORM") (pinfunction "NORM_NORM") (pintype "passive"))
      (node (ref "J3") (pin "GND") (pinfunction "GND_GND") (pintype "passive"))
      (node (ref "J4") (pin "GND") (pinfunction "GND_GND") (pintype "passive"))
      (node (ref "J5") (pin "GND") (pinfunction "GND_GND") (pintype "passive"))
      (node (ref "J6") (pin "GND") (pinfunction "GND_GND") (pintype "passive"))
      (node (ref "J7") (pin "GND") (pinfunction "GND_GND") (pintype "passive"))
      (node (ref "J8") (pin "GND") (pinfunction "GND_GND") (pintype "passive"))
      (node (ref "J9") (pin "GND") (pinfunction "GND_GND") (pintype "passive"))
      (node (ref "JP1") (pin "2") (pinfunction "2_2") (pintype "passive"))
      (node (ref "JP2") (pin "3") (pinfunction "3_3") (pintype "passive"))
      (node (ref "JP2") (pin "5") (pinfunction "5_5") (pintype "passive"))
      (node (ref "JP2") (pin "9") (pinfunction "9_9") (pintype "passive"))
      (node (ref "L1") (pin "A") (pinfunction "A_A") (pintype "passive"))
      (node (ref "L2") (pin "A") (pinfunction "A_A") (pintype "passive"))
      (node (ref "L3") (pin "A") (pinfunction "A_A") (pintype "passive"))
      (node (ref "L4") (pin "A") (pinfunction "A_A") (pintype "passive"))
      (node (ref "PITCH") (pin "P$1") (pinfunction "1_P$1") (pintype "passive"))
      (node (ref "POSITION") (pin "P$3") (pinfunction "3_P$3") (pintype "passive"))
      (node (ref "Q1") (pin "E") (pinfunction "E_E") (pintype "passive"))
      (node (ref "Q2") (pin "E") (pinfunction "E_E") (pintype "passive"))
      (node (ref "Q3") (pin "GND") (pinfunction "GND_GND") (pintype "bidirectional"))
      (node (ref "R13") (pin "1") (pinfunction "1_1") (pintype "passive"))
      (node (ref "R50") (pin "1") (pinfunction "1_1") (pintype "passive"))
      (node (ref "R54") (pin "1") (pinfunction "1_1") (pintype "passive"))
      (node (ref "R56") (pin "1") (pinfunction "1_1") (pintype "passive"))
      (node (ref "R59") (pin "1") (pinfunction "1_1") (pintype "passive"))
      (node (ref "SIZE") (pin "P$1") (pinfunction "1_P$1") (pintype "passive"))
      (node (ref "SW2") (pin "1") (pinfunction "1_1") (pintype "passive"))
      (node (ref "SW2") (pin "2") (pinfunction "2_2") (pintype "passive"))
      (node (ref "SW3") (pin "1") (pinfunction "1_1") (pintype "passive"))
      (node (ref "SW3") (pin "2") (pinfunction "2_2") (pintype "passive"))
      (node (ref "TEXTURE") (pin "P$1") (pinfunction "1_P$1") (pintype "passive"))
      (node (ref "U$1") (pin "3") (pinfunction "2_3") (pintype "bidirectional"))
      (node (ref "U$1") (pin "4") (pinfunction "4_4") (pintype "bidirectional"))
      (node (ref "U$1") (pin "K") (pinfunction "C_K") (pintype "passive"))
      (node (ref "U$2") (pin "GND1") (pinfunction "GND_GND1") (pintype "bidirectional"))
      (node (ref "U$2") (pin "GND2") (pinfunction "GND_GND2") (pintype "bidirectional"))
      (node (ref "U$2") (pin "GND3") (pinfunction "GND_GND3") (pintype "bidirectional"))
      (node (ref "U$2") (pin "GND4") (pinfunction "GND_GND4") (pintype "bidirectional"))
      (node (ref "U$2") (pin "GND5") (pinfunction "GND_GND5") (pintype "bidirectional"))
      (node (ref "U$2") (pin "GND6") (pinfunction "GND_GND6") (pintype "bidirectional"))
      (node (ref "U$3") (pin "GND") (pinfunction "GND_GND") (pintype "bidirectional"))
      (node (ref "U$4") (pin "3") (pinfunction "P$1_3") (pintype "bidirectional"))
    )
    (net (code "9") (name "I2C_SCL") (class "Default")
      (node (ref "IC5") (pin "29") (pinfunction "PB10/SPI2_SCK/I2S_SCK/I2C2_SCL/USART3_TX_29") (pintype "bidirectional"))
      (node (ref "IC8") (pin "24") (pinfunction "SCLK_24") (pintype "bidirectional"))
      (node (ref "R40") (pin "1") (pinfunction "1_1") (pintype "passive"))
    )
    (net (code "10") (name "I2C_SDA") (class "Default")
      (node (ref "IC5") (pin "30") (pinfunction "PB11/I2C2_SDA/USART3_RX_30") (pintype "bidirectional"))
      (node (ref "IC8") (pin "23") (pinfunction "SDIN_23") (pintype "bidirectional"))
      (node (ref "R41") (pin "1") (pinfunction "1_1") (pintype "passive"))
    )
    (net (code "11") (name "I2S_LRCK") (class "Default")
      (node (ref "IC5") (pin "33") (pinfunction "PB12/SPI2_NSS/I2S2_WS/I2C2_SMBA/USART3_CK/TIM1_BKIN_33") (pintype "bidirectional"))
      (node (ref "IC8") (pin "5") (pinfunction "DACLRC_5") (pintype "bidirectional"))
      (node (ref "IC8") (pin "7") (pinfunction "ADCLRC_7") (pintype "bidirectional"))
    )
    (net (code "12") (name "I2S_SCK") (class "Default")
      (node (ref "IC5") (pin "34") (pinfunction "PB13/SPI2_SCK/I2S2_SCK/USART3_CTS/TIM1_CH1N_34") (pintype "bidirectional"))
      (node (ref "IC8") (pin "3") (pinfunction "BCLK_3") (pintype "bidirectional"))
    )
    (net (code "13") (name "I2S_SIN") (class "Default")
      (node (ref "IC5") (pin "35") (pinfunction "PB14/SPI2_MISO/USART3_RTS/TIM1_CH2N_35") (pintype "bidirectional"))
      (node (ref "IC8") (pin "6") (pinfunction "ADCDAT_6") (pintype "bidirectional"))
    )
    (net (code "14") (name "I2S_SOUT") (class "Default")
      (node (ref "IC5") (pin "36") (pinfunction "PB15/SPI2_MOSI/I2S2_SD/TIM1_CH3N_36") (pintype "bidirectional"))
      (node (ref "IC8") (pin "4") (pinfunction "DACDAT_4") (pintype "bidirectional"))
    )
    (net (code "15") (name "JTCK") (class "Default")
      (node (ref "IC5") (pin "49") (pinfunction "PA14/JTCK-SWCLK_49") (pintype "bidirectional"))
      (node (ref "JP2") (pin "4") (pinfunction "4_4") (pintype "passive"))
    )
    (net (code "16") (name "JTDI") (class "Default")
      (node (ref "IC5") (pin "50") (pinfunction "PA15/JTDI/SPI3_NSS/I2S3_WS_50") (pintype "bidirectional"))
      (node (ref "JP2") (pin "8") (pinfunction "8_8") (pintype "passive"))
    )
    (net (code "17") (name "JTDO") (class "Default")
      (node (ref "IC5") (pin "55") (pinfunction "PB3/JTDO/SPI3_SCK/I2S3_SCK_55") (pintype "bidirectional"))
      (node (ref "JP2") (pin "6") (pinfunction "6_6") (pintype "passive"))
    )
    (net (code "18") (name "JTMS") (class "Default")
      (node (ref "IC5") (pin "46") (pinfunction "PA13/JTMS-SWDAT_46") (pintype "bidirectional"))
      (node (ref "JP2") (pin "2") (pinfunction "2_2") (pintype "passive"))
    )
    (net (code "19") (name "LED_DATA") (class "Default")
      (node (ref "IC11") (pin "14") (pinfunction "SER_14") (pintype "input"))
      (node (ref "IC5") (pin "57") (pinfunction "PB5/I2C1_SMBA/SPI1_MOSI/SPI3_MOSI/I2S3_SD_57") (pintype "bidirectional"))
    )
    (net (code "20") (name "LED_EN") (class "Default")
      (node (ref "IC11") (pin "12") (pinfunction "RCK_12") (pintype "input"))
      (node (ref "IC5") (pin "24") (pinfunction "PC4/ADC14_24") (pintype "bidirectional"))
    )
    (net (code "21") (name "LED_REC") (class "Default")
      (node (ref "IC5") (pin "62") (pinfunction "PB9/SPI2_NSS/I2S2_WS/I2C1_SDA/TIM4_CH4_62") (pintype "bidirectional"))
      (node (ref "R1") (pin "1") (pinfunction "1_1") (pintype "passive"))
      (node (ref "R2") (pin "1") (pinfunction "1_1") (pintype "passive"))
    )
    (net (code "22") (name "LED_SCK") (class "Default")
      (node (ref "IC11") (pin "11") (pinfunction "SCK_11") (pintype "input"))
      (node (ref "IC5") (pin "25") (pinfunction "PC5/ADC15_25") (pintype "bidirectional"))
    )
    (net (code "23") (name "LIN") (class "Default")
      (node (ref "C37") (pin "+") (pinfunction "+_+") (pintype "passive"))
      (node (ref "IC8") (pin "20") (pinfunction "LLINEIN_20") (pintype "bidirectional"))
    )
    (net (code "24") (name "LOUT") (class "Default")
      (node (ref "C33") (pin "+") (pinfunction "+_+") (pintype "passive"))
      (node (ref "IC8") (pin "12") (pinfunction "LOUT_12") (pintype "bidirectional"))
    )
    (net (code "25") (name "Net-(C33-Pad-)") (class "Default")
      (node (ref "C33") (pin "-") (pinfunction "-_-") (pintype "passive"))
      (node (ref "R51") (pin "2") (pinfunction "2_2") (pintype "passive"))
      (node (ref "R59") (pin "2") (pinfunction "2_2") (pintype "passive"))
    )
    (net (code "26") (name "Net-(C36-Pad-)") (class "Default")
      (node (ref "C36") (pin "-") (pinfunction "-_-") (pintype "passive"))
      (node (ref "C43") (pin "1") (pinfunction "1_1") (pintype "passive"))
      (node (ref "R53") (pin "1") (pinfunction "1_1") (pintype "passive"))
      (node (ref "R54") (pin "2") (pinfunction "2_2") (pintype "passive"))
    )
    (net (code "27") (name "Net-(C37-Pad-)") (class "Default")
      (node (ref "C37") (pin "-") (pinfunction "-_-") (pintype "passive"))
      (node (ref "C44") (pin "1") (pinfunction "1_1") (pintype "passive"))
      (node (ref "R55") (pin "1") (pinfunction "1_1") (pintype "passive"))
      (node (ref "R56") (pin "2") (pinfunction "2_2") (pintype "passive"))
    )
    (net (code "28") (name "Net-(C41-Pad-)") (class "Default")
      (node (ref "C41") (pin "-") (pinfunction "-_-") (pintype "passive"))
      (node (ref "R50") (pin "2") (pinfunction "2_2") (pintype "passive"))
      (node (ref "R52") (pin "2") (pinfunction "2_2") (pintype "passive"))
    )
    (net (code "29") (name "Net-(D1-PadC)") (class "Default")
      (node (ref "D1") (pin "C") (pinfunction "C_C") (pintype "passive"))
      (node (ref "U$2") (pin "V-") (pinfunction "V--_V-") (pintype "bidirectional"))
      (node (ref "U$2") (pin "V--") (pinfunction "V--_V--") (pintype "bidirectional"))
    )
    (net (code "30") (name "Net-(D2-PadA)") (class "Default")
      (node (ref "D2") (pin "A") (pinfunction "A_A") (pintype "passive"))
      (node (ref "U$2") (pin "V+") (pinfunction "V++_V+") (pintype "bidirectional"))
      (node (ref "U$2") (pin "V++") (pinfunction "V++_V++") (pintype "bidirectional"))
    )
    (net (code "31") (name "Net-(DENSITY-2)") (class "Default")
      (node (ref "DENSITY") (pin "P$2") (pinfunction "2_P$2") (pintype "passive"))
      (node (ref "R33") (pin "2") (pinfunction "2_2") (pintype "passive"))
    )
    (net (code "32") (name "Net-(IC2-VIN)") (class "Default")
      (node (ref "C2") (pin "+") (pinfunction "+_+") (pintype "passive"))
      (node (ref "IC2") (pin "2") (pinfunction "VIN_2") (pintype "input"))
      (node (ref "R11") (pin "2") (pinfunction "2_2") (pintype "passive"))
    )
    (net (code "33") (name "Net-(IC3A--IN)") (class "Default")
      (node (ref "C22") (pin "1") (pinfunction "1_1") (pintype "passive"))
      (node (ref "IC3") (pin "2") (pinfunction "-IN_2") (pintype "input"))
      (node (ref "R31") (pin "2") (pinfunction "2_2") (pintype "passive"))
      (node (ref "R32") (pin "1") (pinfunction "1_1") (pintype "passive"))
      (node (ref "R33") (pin "1") (pinfunction "1_1") (pintype "passive"))
    )
    (net (code "34") (name "Net-(IC3B--IN)") (class "Default")
      (node (ref "C9") (pin "1") (pinfunction "1_1") (pintype "passive"))
      (node (ref "IC3") (pin "6") (pinfunction "-IN_6") (pintype "input"))
      (node (ref "R27") (pin "2") (pinfunction "2_2") (pintype "passive"))
      (node (ref "R28") (pin "1") (pinfunction "1_1") (pintype "passive"))
      (node (ref "R29") (pin "1") (pinfunction "1_1") (pintype "passive"))
    )
    (net (code "35") (name "Net-(IC4A--IN)") (class "Default")
      (node (ref "C20") (pin "1") (pinfunction "1_1") (pintype "passive"))
      (node (ref "IC4") (pin "2") (pinfunction "-IN_2") (pintype "input"))
      (node (ref "R34") (pin "2") (pinfunction "2_2") (pintype "passive"))
      (node (ref "R36") (pin "1") (pinfunction "1_1") (pintype "passive"))
      (node (ref "R38") (pin "1") (pinfunction "1_1") (pintype "passive"))
    )
    (net (code "36") (name "Net-(IC4B--IN)") (class "Default")
      (node (ref "C21") (pin "1") (pinfunction "1_1") (pintype "passive"))
      (node (ref "IC4") (pin "6") (pinfunction "-IN_6") (pintype "input"))
      (node (ref "R35") (pin "2") (pinfunction "2_2") (pintype "passive"))
      (node (ref "R37") (pin "1") (pinfunction "1_1") (pintype "passive"))
      (node (ref "R39") (pin "1") (pinfunction "1_1") (pintype "passive"))
    )
    (net (code "37") (name "Net-(IC4C--IN)") (class "Default")
      (node (ref "C11") (pin "1") (pinfunction "1_1") (pintype "passive"))
      (node (ref "IC4") (pin "9") (pinfunction "-IN_9") (pintype "input"))
      (node (ref "R23") (pin "1") (pinfunction "1_1") (pintype "passive"))
      (node (ref "R24") (pin "1") (pinfunction "1_1") (pintype "passive"))
      (node (ref "R26") (pin "2") (pinfunction "2_2") (pintype "passive"))
    )
    (net (code "38") (name "Net-(IC4D--IN)") (class "Default")
      (node (ref "C10") (pin "1") (pinfunction "1_1") (pintype "passive"))
      (node (ref "IC4") (pin "13") (pinfunction "-IN_13") (pintype "input"))
      (node (ref "R21") (pin "1") (pinfunction "1_1") (pintype "passive"))
      (node (ref "R22") (pin "1") (pinfunction "1_1") (pintype "passive"))
      (node (ref "R25") (pin "2") (pinfunction "2_2") (pintype "passive"))
    )
    (net (code "39") (name "Net-(IC5-PD0{slash}OSC_IN)") (class "Default")
      (node (ref "IC5") (pin "5") (pinfunction "PD0/OSC_IN_5") (pintype "bidirectional"))
      (node (ref "Q3") (pin "X2") (pinfunction "X2_X2") (pintype "bidirectional"))
    )
    (net (code "40") (name "Net-(IC5-PD1{slash}OSC_OUT)") (class "Default")
      (node (ref "IC5") (pin "6") (pinfunction "PD1/OSC_OUT_6") (pintype "bidirectional"))
      (node (ref "Q3") (pin "X1") (pinfunction "X1_X1") (pintype "bidirectional"))
    )
    (net (code "41") (name "Net-(IC5-VCAP_1)") (class "Default")
      (node (ref "C24") (pin "1") (pinfunction "1_1") (pintype "passive"))
      (node (ref "IC5") (pin "31") (pinfunction "VCAP_1_31") (pintype "power_in"))
    )
    (net (code "42") (name "Net-(IC5-VCAP_2)") (class "Default")
      (node (ref "C19") (pin "1") (pinfunction "1_1") (pintype "passive"))
      (node (ref "IC5") (pin "47") (pinfunction "VCAP_2_47") (pintype "power_in"))
    )
    (net (code "43") (name "Net-(IC8-VMID)") (class "Default")
      (node (ref "C34") (pin "1") (pinfunction "1_1") (pintype "passive"))
      (node (ref "C35") (pin "+") (pinfunction "+_+") (pintype "passive"))
      (node (ref "IC8") (pin "16") (pinfunction "VMID_16") (pintype "bidirectional"))
    )
    (net (code "44") (name "Net-(IC8-XTI{slash}MCLK)") (class "Default")
      (node (ref "IC8") (pin "25") (pinfunction "XTI/MCLK_25") (pintype "bidirectional"))
      (node (ref "U$3") (pin "X1") (pinfunction "X1_X1") (pintype "bidirectional"))
    )
    (net (code "45") (name "Net-(IC8-XTO)") (class "Default")
      (node (ref "IC8") (pin "26") (pinfunction "XTO_26") (pintype "bidirectional"))
      (node (ref "U$3") (pin "X2") (pinfunction "X2_X2") (pintype "bidirectional"))
    )
    (net (code "46") (name "Net-(IC9A--IN)") (class "Default")
      (node (ref "IC9") (pin "2") (pinfunction "-IN_2") (pintype "input"))
      (node (ref "R46") (pin "2") (pinfunction "2_2") (pintype "passive"))
      (node (ref "R57") (pin "1") (pinfunction "1_1") (pintype "passive"))
    )
    (net (code "47") (name "Net-(IC9A-OUT)") (class "Default")
      (node (ref "IC9") (pin "1") (pinfunction "OUT_1") (pintype "output"))
      (node (ref "R42") (pin "2") (pinfunction "S_2") (pintype "passive"))
      (node (ref "R42") (pin "3") (pinfunction "E_3") (pintype "passive"))
      (node (ref "R55") (pin "2") (pinfunction "2_2") (pintype "passive"))
    )
    (net (code "48") (name "Net-(IC9B--IN)") (class "Default")
      (node (ref "IC9") (pin "6") (pinfunction "-IN_6") (pintype "input"))
      (node (ref "R47") (pin "2") (pinfunction "2_2") (pintype "passive"))
      (node (ref "R58") (pin "1") (pinfunction "1_1") (pintype "passive"))
    )
    (net (code "49") (name "Net-(IC9B-OUT)") (class "Default")
      (node (ref "IC9") (pin "7") (pinfunction "OUT_7") (pintype "output"))
      (node (ref "R42") (pin "2P") (pinfunction "S_2P") (pintype "passive"))
      (node (ref "R42") (pin "3P") (pinfunction "E_3P") (pintype "passive"))
      (node (ref "R53") (pin "2") (pinfunction "2_2") (pintype "passive"))
    )
    (net (code "50") (name "Net-(IC10A--IN)") (class "Default")
      (node (ref "C40") (pin "1") (pinfunction "1_1") (pintype "passive"))
      (node (ref "IC10") (pin "2") (pinfunction "-IN_2") (pintype "input"))
      (node (ref "R49") (pin "2") (pinfunction "2_2") (pintype "passive"))
      (node (ref "R51") (pin "1") (pinfunction "1_1") (pintype "passive"))
    )
    (net (code "51") (name "Net-(IC10A-OUT)") (class "Default")
      (node (ref "C40") (pin "2") (pinfunction "2_2") (pintype "passive"))
      (node (ref "IC10") (pin "1") (pinfunction "OUT_1") (pintype "output"))
      (node (ref "R49") (pin "1") (pinfunction "1_1") (pintype "passive"))
      (node (ref "R61") (pin "2") (pinfunction "2_2") (pintype "passive"))
    )
    (net (code "52") (name "Net-(IC10B--IN)") (class "Default")
      (node (ref "C42") (pin "1") (pinfunction "1_1") (pintype "passive"))
      (node (ref "IC10") (pin "6") (pinfunction "-IN_6") (pintype "input"))
      (node (ref "R48") (pin "2") (pinfunction "2_2") (pintype "passive"))
      (node (ref "R52") (pin "1") (pinfunction "1_1") (pintype "passive"))
    )
    (net (code "53") (name "Net-(IC10B-OUT)") (class "Default")
      (node (ref "C42") (pin "2") (pinfunction "2_2") (pintype "passive"))
      (node (ref "IC10") (pin "7") (pinfunction "OUT_7") (pintype "output"))
      (node (ref "R48") (pin "1") (pinfunction "1_1") (pintype "passive"))
      (node (ref "R62") (pin "2") (pinfunction "2_2") (pintype "passive"))
    )
    (net (code "54") (name "Net-(IC11-QA)") (class "Default")
      (node (ref "IC11") (pin "15") (pinfunction "QA_15") (pintype "tri_state"))
      (node (ref "R10") (pin "2") (pinfunction "2_2") (pintype "passive"))
    )
    (net (code "55") (name "Net-(IC11-QB)") (class "Default")
      (node (ref "IC11") (pin "1") (pinfunction "QB_1") (pintype "tri_state"))
      (node (ref "R9") (pin "2") (pinfunction "2_2") (pintype "passive"))
    )
    (net (code "56") (name "Net-(IC11-QC)") (class "Default")
      (node (ref "IC11") (pin "2") (pinfunction "QC_2") (pintype "tri_state"))
      (node (ref "R8") (pin "2") (pinfunction "2_2") (pintype "passive"))
    )
    (net (code "57") (name "Net-(IC11-QD)") (class "Default")
      (node (ref "IC11") (pin "3") (pinfunction "QD_3") (pintype "tri_state"))
      (node (ref "R7") (pin "2") (pinfunction "2_2") (pintype "passive"))
    )
    (net (code "58") (name "Net-(IC11-QE)") (class "Default")
      (node (ref "IC11") (pin "4") (pinfunction "QE_4") (pintype "tri_state"))
      (node (ref "R6") (pin "2") (pinfunction "2_2") (pintype "passive"))
    )
    (net (code "59") (name "Net-(IC11-QF)") (class "Default")
      (node (ref "IC11") (pin "5") (pinfunction "QF_5") (pintype "tri_state"))
      (node (ref "R5") (pin "2") (pinfunction "2_2") (pintype "passive"))
    )
    (net (code "60") (name "Net-(IC11-QG)") (class "Default")
      (node (ref "IC11") (pin "6") (pinfunction "QG_6") (pintype "tri_state"))
      (node (ref "R3") (pin "2") (pinfunction "2_2") (pintype "passive"))
    )
    (net (code "61") (name "Net-(IC11-QH)") (class "Default")
      (node (ref "IC11") (pin "7") (pinfunction "QH_7") (pintype "tri_state"))
      (node (ref "R4") (pin "2") (pinfunction "2_2") (pintype "passive"))
    )
    (net (code "62") (name "Net-(J1-PadTIP)") (class "Default")
      (node (ref "J1") (pin "TIP") (pinfunction "TIP_TIP") (pintype "passive"))
      (node (ref "R12") (pin "1") (pinfunction "1_1") (pintype "passive"))
    )
    (net (code "63") (name "Net-(J2-PadTIP)") (class "Default")
      (node (ref "J2") (pin "TIP") (pinfunction "TIP_TIP") (pintype "passive"))
      (node (ref "R15") (pin "1") (pinfunction "1_1") (pintype "passive"))
    )
    (net (code "64") (name "Net-(J3-PadTIP)") (class "Default")
      (node (ref "J3") (pin "TIP") (pinfunction "TIP_TIP") (pintype "passive"))
      (node (ref "R29") (pin "2") (pinfunction "2_2") (pintype "passive"))
    )
    (net (code "65") (name "Net-(J4-PadTIP)") (class "Default")
      (node (ref "J4") (pin "TIP") (pinfunction "TIP_TIP") (pintype "passive"))
      (node (ref "R21") (pin "2") (pinfunction "2_2") (pintype "passive"))
    )
    (net (code "66") (name "Net-(J5-PadTIP)") (class "Default")
      (node (ref "J5") (pin "TIP") (pinfunction "TIP_TIP") (pintype "passive"))
      (node (ref "R38") (pin "2") (pinfunction "2_2") (pintype "passive"))
    )
    (net (code "67") (name "Net-(J6-PadTIP)") (class "Default")
      (node (ref "J6") (pin "TIP") (pinfunction "TIP_TIP") (pintype "passive"))
      (node (ref "R39") (pin "2") (pinfunction "2_2") (pintype "passive"))
    )
    (net (code "68") (name "Net-(J7-PadTIP)") (class "Default")
      (node (ref "J7") (pin "TIP") (pinfunction "TIP_TIP") (pintype "passive"))
      (node (ref "J8") (pin "NORM") (pinfunction "NORM_NORM") (pintype "passive"))
      (node (ref "R57") (pin "2") (pinfunction "2_2") (pintype "passive"))
    )
    (net (code "69") (name "Net-(J8-PadTIP)") (class "Default")
      (node (ref "J8") (pin "TIP") (pinfunction "TIP_TIP") (pintype "passive"))
      (node (ref "R58") (pin "2") (pinfunction "2_2") (pintype "passive"))
    )
    (net (code "70") (name "Net-(J9-PadTIP)") (class "Default")
      (node (ref "J9") (pin "TIP") (pinfunction "TIP_TIP") (pintype "passive"))
      (node (ref "R32") (pin "2") (pinfunction "2_2") (pintype "passive"))
    )
    (net (code "71") (name "Net-(J10-PadTIP)") (class "Default")
      (node (ref "J10") (pin "TIP") (pinfunction "TIP_TIP") (pintype "passive"))
      (node (ref "R24") (pin "2") (pinfunction "2_2") (pintype "passive"))
    )
    (net (code "72") (name "Net-(J11-PadTIP)") (class "Default")
      (node (ref "J11") (pin "TIP") (pinfunction "TIP_TIP") (pintype "passive"))
      (node (ref "R61") (pin "1") (pinfunction "1_1") (pintype "passive"))
    )
    (net (code "73") (name "Net-(J12-PadTIP)") (class "Default")
      (node (ref "J12") (pin "TIP") (pinfunction "TIP_TIP") (pintype "passive"))
      (node (ref "R62") (pin "1") (pinfunction "1_1") (pintype "passive"))
    )
    (net (code "74") (name "Net-(L1-PadC1)") (class "Default")
      (node (ref "L1") (pin "C1") (pinfunction "C1_C1") (pintype "passive"))
      (node (ref "R4") (pin "1") (pinfunction "1_1") (pintype "passive"))
    )
    (net (code "75") (name "Net-(L1-PadC2)") (class "Default")
      (node (ref "L1") (pin "C2") (pinfunction "C2_C2") (pintype "passive"))
      (node (ref "R3") (pin "1") (pinfunction "1_1") (pintype "passive"))
    )
    (net (code "76") (name "Net-(L2-PadC1)") (class "Default")
      (node (ref "L2") (pin "C1") (pinfunction "C1_C1") (pintype "passive"))
      (node (ref "R5") (pin "1") (pinfunction "1_1") (pintype "passive"))
    )
    (net (code "77") (name "Net-(L2-PadC2)") (class "Default")
      (node (ref "L2") (pin "C2") (pinfunction "C2_C2") (pintype "passive"))
      (node (ref "R6") (pin "1") (pinfunction "1_1") (pintype "passive"))
    )
    (net (code "78") (name "Net-(L3-PadC1)") (class "Default")
      (node (ref "L3") (pin "C1") (pinfunction "C1_C1") (pintype "passive"))
      (node (ref "R7") (pin "1") (pinfunction "1_1") (pintype "passive"))
    )
    (net (code "79") (name "Net-(L3-PadC2)") (class "Default")
      (node (ref "L3") (pin "C2") (pinfunction "C2_C2") (pintype "passive"))
      (node (ref "R8") (pin "1") (pinfunction "1_1") (pintype "passive"))
    )
    (net (code "80") (name "Net-(L4-PadC1)") (class "Default")
      (node (ref "L4") (pin "C1") (pinfunction "C1_C1") (pintype "passive"))
      (node (ref "R9") (pin "1") (pinfunction "1_1") (pintype "passive"))
    )
    (net (code "81") (name "Net-(L4-PadC2)") (class "Default")
      (node (ref "L4") (pin "C2") (pinfunction "C2_C2") (pintype "passive"))
      (node (ref "R10") (pin "1") (pinfunction "1_1") (pintype "passive"))
    )
    (net (code "82") (name "Net-(POSITION-2)") (class "Default")
      (node (ref "POSITION") (pin "P$2") (pinfunction "2_P$2") (pintype "passive"))
      (node (ref "R28") (pin "2") (pinfunction "2_2") (pintype "passive"))
    )
    (net (code "83") (name "Net-(Q1-PadB)") (class "Default")
      (node (ref "Q1") (pin "B") (pinfunction "B_B") (pintype "passive"))
      (node (ref "R12") (pin "2") (pinfunction "2_2") (pintype "passive"))
    )
    (net (code "84") (name "Net-(Q2-PadB)") (class "Default")
      (node (ref "Q2") (pin "B") (pinfunction "B_B") (pintype "passive"))
      (node (ref "R15") (pin "2") (pinfunction "2_2") (pintype "passive"))
    )
    (net (code "85") (name "Net-(R1-Pad2)") (class "Default")
      (node (ref "R1") (pin "2") (pinfunction "2_2") (pintype "passive"))
      (node (ref "R2") (pin "2") (pinfunction "2_2") (pintype "passive"))
      (node (ref "U$1") (pin "A") (pinfunction "A_A") (pintype "passive"))
    )
    (net (code "86") (name "Net-(R42A-A)") (class "Default")
      (node (ref "R42") (pin "1P") (pinfunction "A_1P") (pintype "passive"))
      (node (ref "R47") (pin "1") (pinfunction "1_1") (pintype "passive"))
    )
    (net (code "87") (name "Net-(R42B-A)") (class "Default")
      (node (ref "R42") (pin "1") (pinfunction "A_1") (pintype "passive"))
      (node (ref "R46") (pin "1") (pinfunction "1_1") (pintype "passive"))
    )
    (net (code "88") (name "PITCH_POT") (class "Default")
      (node (ref "IC5") (pin "9") (pinfunction "PC1/ADC11_9") (pintype "bidirectional"))
      (node (ref "PITCH") (pin "P$2") (pinfunction "2_P$2") (pintype "passive"))
    )
    (net (code "89") (name "PLAY") (class "Default")
      (node (ref "IC5") (pin "58") (pinfunction "PB6/I2C1_SCL/TIM4_CH1/USART1_TX_58") (pintype "bidirectional"))
      (node (ref "Q2") (pin "C") (pinfunction "C_C") (pintype "passive"))
      (node (ref "R16") (pin "1") (pinfunction "1_1") (pintype "passive"))
    )
    (net (code "90") (name "POSITION_POT_CV") (class "Default")
      (node (ref "C9") (pin "2") (pinfunction "2_2") (pintype "passive"))
      (node (ref "IC3") (pin "7") (pinfunction "OUT_7") (pintype "output"))
      (node (ref "IC5") (pin "16") (pinfunction "PA2/USART2_TX/ADC2/TIM2_CH3_16") (pintype "bidirectional"))
      (node (ref "R27") (pin "1") (pinfunction "1_1") (pintype "passive"))
    )
    (net (code "91") (name "REC") (class "Default")
      (node (ref "IC5") (pin "59") (pinfunction "PB7/I2C1_SDA/TIM4_CH2/USART1_RX_59") (pintype "bidirectional"))
      (node (ref "Q1") (pin "C") (pinfunction "C_C") (pintype "passive"))
      (node (ref "R14") (pin "1") (pinfunction "1_1") (pintype "passive"))
    )
    (net (code "92") (name "RESET") (class "Default")
      (node (ref "IC5") (pin "7") (pinfunction "NRST_7") (pintype "bidirectional"))
      (node (ref "JP1") (pin "1") (pinfunction "1_1") (pintype "passive"))
      (node (ref "JP2") (pin "10") (pinfunction "10_10") (pintype "passive"))
      (node (ref "R17") (pin "1") (pinfunction "1_1") (pintype "passive"))
    )
    (net (code "93") (name "RIN") (class "Default")
      (node (ref "C36") (pin "+") (pinfunction "+_+") (pintype "passive"))
      (node (ref "IC8") (pin "19") (pinfunction "RLINEIN_19") (pintype "bidirectional"))
    )
    (net (code "94") (name "ROUT") (class "Default")
      (node (ref "C41") (pin "+") (pinfunction "+_+") (pintype "passive"))
      (node (ref "IC8") (pin "13") (pinfunction "ROUT_13") (pintype "bidirectional"))
    )
    (net (code "95") (name "RX") (class "Default")
      (node (ref "IC5") (pin "43") (pinfunction "PA10/USART1_RX/TIM1_CH3_43") (pintype "bidirectional"))
      (node (ref "U$4") (pin "2") (pinfunction "P$1_2") (pintype "bidirectional"))
    )
    (net (code "96") (name "SIZE_CV") (class "Default")
      (node (ref "C10") (pin "2") (pinfunction "2_2") (pintype "passive"))
      (node (ref "IC4") (pin "14") (pinfunction "OUT_14") (pintype "output"))
      (node (ref "IC5") (pin "15") (pinfunction "PA1/USART2_RTS/UART4_RX/ADC1/TIM2_CH2_15") (pintype "bidirectional"))
      (node (ref "R25") (pin "1") (pinfunction "1_1") (pintype "passive"))
    )
    (net (code "97") (name "SIZE_POT") (class "Default")
      (node (ref "IC5") (pin "8") (pinfunction "PC0/ADC10_8") (pintype "bidirectional"))
      (node (ref "SIZE") (pin "P$2") (pinfunction "2_P$2") (pintype "passive"))
    )
    (net (code "98") (name "SW_LOAD") (class "Default")
      (node (ref "IC5") (pin "51") (pinfunction "PC10/SPI3_SCK/I2S3_SCK/UART4_TX_51") (pintype "bidirectional"))
      (node (ref "SW3") (pin "3") (pinfunction "3_3") (pintype "passive"))
      (node (ref "SW3") (pin "4") (pinfunction "4_4") (pintype "passive"))
    )
    (net (code "99") (name "SW_MODE") (class "Default")
      (node (ref "IC5") (pin "52") (pinfunction "PC11/UART4_RX/SPI3_MISO/USART3_RX_52") (pintype "bidirectional"))
      (node (ref "SW2") (pin "3") (pinfunction "3_3") (pintype "passive"))
      (node (ref "SW2") (pin "4") (pinfunction "4_4") (pintype "passive"))
    )
    (net (code "100") (name "SW_REC") (class "Default")
      (node (ref "IC5") (pin "61") (pinfunction "PB8/TIM4_CH3/I2C1_SCL_61") (pintype "bidirectional"))
      (node (ref "U$1") (pin "1") (pinfunction "3_1") (pintype "bidirectional"))
      (node (ref "U$1") (pin "2") (pinfunction "1_2") (pintype "bidirectional"))
    )
    (net (code "101") (name "TEXTURE_CV") (class "Default")
      (node (ref "C11") (pin "2") (pinfunction "2_2") (pintype "passive"))
      (node (ref "IC4") (pin "8") (pinfunction "OUT_8") (pintype "output"))
      (node (ref "IC5") (pin "14") (pinfunction "PA0-WKUP/USART2_CTS/UART4_TX/ADC0/TIM2_CH1_ETR_14") (pintype "bidirectional"))
      (node (ref "R26") (pin "1") (pinfunction "1_1") (pintype "passive"))
    )
    (net (code "102") (name "TEXTURE_POT") (class "Default")
      (node (ref "IC5") (pin "22") (pinfunction "PA6/SPI1_MISO/ADC6/TIM3_CH1_22") (pintype "bidirectional"))
      (node (ref "TEXTURE") (pin "P$2") (pinfunction "2_P$2") (pintype "passive"))
    )
    (net (code "103") (name "TX") (class "Default")
      (node (ref "IC5") (pin "42") (pinfunction "PA9/USART1_TX/TIM1_CH2_42") (pintype "bidirectional"))
      (node (ref "U$4") (pin "1") (pinfunction "P$1_1") (pintype "bidirectional"))
    )
    (net (code "104") (name "VBAT") (class "Default")
      (node (ref "IC5") (pin "1") (pinfunction "VBAT_1") (pintype "power_in"))
    )
    (net (code "105") (name "VCC") (class "Default")
      (node (ref "C1") (pin "+") (pinfunction "+_+") (pintype "passive"))
      (node (ref "C38") (pin "1") (pinfunction "1_1") (pintype "passive"))
      (node (ref "C39") (pin "1") (pinfunction "1_1") (pintype "passive"))
      (node (ref "D2") (pin "C") (pinfunction "C_C") (pintype "passive"))
      (node (ref "IC10") (pin "8") (pinfunction "V+_8") (pintype "power_in"))
      (node (ref "IC7") (pin "3") (pinfunction "VIN_3") (pintype "input"))
      (node (ref "IC9") (pin "8") (pinfunction "V+_8") (pintype "power_in"))
      (node (ref "R11") (pin "1") (pinfunction "1_1") (pintype "passive"))
    )
    (net (code "106") (name "VEE") (class "Default")
      (node (ref "C13") (pin "-") (pinfunction "-_-") (pintype "passive"))
      (node (ref "C45") (pin "2") (pinfunction "2_2") (pintype "passive"))
      (node (ref "C46") (pin "2") (pinfunction "2_2") (pintype "passive"))
      (node (ref "D1") (pin "A") (pinfunction "A_A") (pintype "passive"))
      (node (ref "IC10") (pin "4") (pinfunction "V-_4") (pintype "power_in"))
      (node (ref "IC9") (pin "4") (pinfunction "V-_4") (pintype "power_in"))
      (node (ref "R30") (pin "1") (pinfunction "1_1") (pintype "passive"))
    )
    (net (code "107") (name "V_OCT") (class "Default")
      (node (ref "C20") (pin "2") (pinfunction "2_2") (pintype "passive"))
      (node (ref "IC4") (pin "1") (pinfunction "OUT_1") (pintype "output"))
      (node (ref "IC5") (pin "20") (pinfunction "PA4/SPI1_NSS/SPI3_NSS/USART2_CK/I2S3_WS/ADC4/DAC1_20") (pintype "bidirectional"))
      (node (ref "R34") (pin "1") (pinfunction "1_1") (pintype "passive"))
    )
    (net (code "108") (name "unconnected-(IC5-PA8{slash}USART1_CK{slash}TIM1_CH1{slash}MCO-Pad41)") (class "Default")
      (node (ref "IC5") (pin "41") (pinfunction "PA8/USART1_CK/TIM1_CH1/MCO_41") (pintype "bidirectional"))
    )
    (net (code "109") (name "unconnected-(IC5-PA11{slash}USART1_CTS{slash}CANRX{slash}USBDM{slash}TIM1_CH4-Pad44)") (class "Default")
      (node (ref "IC5") (pin "44") (pinfunction "PA11/USART1_CTS/CANRX/USBDM/TIM1_CH4_44") (pintype "bidirectional"))
    )
    (net (code "110") (name "unconnected-(IC5-PA12{slash}USART1_RTS{slash}CANTX{slash}USBDP{slash}TIM1_ETR-Pad45)") (class "Default")
      (node (ref "IC5") (pin "45") (pinfunction "PA12/USART1_RTS/CANTX/USBDP/TIM1_ETR_45") (pintype "bidirectional"))
    )
    (net (code "111") (name "unconnected-(IC5-PB1{slash}ADC9{slash}TIM3_CH4-Pad27)") (class "Default")
      (node (ref "IC5") (pin "27") (pinfunction "PB1/ADC9/TIM3_CH4_27") (pintype "bidirectional"))
    )
    (net (code "112") (name "unconnected-(IC5-PB4{slash}NJTRST{slash}SPI3_MISO{slash}SPI1_MISO-Pad56)") (class "Default")
      (node (ref "IC5") (pin "56") (pinfunction "PB4/NJTRST/SPI3_MISO/SPI1_MISO_56") (pintype "bidirectional"))
    )
    (net (code "113") (name "unconnected-(IC5-PC2{slash}SPI2_MISO{slash}ADC12-Pad10)") (class "Default")
      (node (ref "IC5") (pin "10") (pinfunction "PC2/SPI2_MISO/ADC12_10") (pintype "bidirectional"))
    )
    (net (code "114") (name "unconnected-(IC5-PC3{slash}SPI2_MOSI{slash}I2S2_SD{slash}ADC13-Pad11)") (class "Default")
      (node (ref "IC5") (pin "11") (pinfunction "PC3/SPI2_MOSI/I2S2_SD/ADC13_11") (pintype "bidirectional"))
    )
    (net (code "115") (name "unconnected-(IC5-PC6{slash}I2S2_MCK-Pad37)") (class "Default")
      (node (ref "IC5") (pin "37") (pinfunction "PC6/I2S2_MCK_37") (pintype "bidirectional"))
    )
    (net (code "116") (name "unconnected-(IC5-PC7{slash}I2S3_MCK-Pad38)") (class "Default")
      (node (ref "IC5") (pin "38") (pinfunction "PC7/I2S3_MCK_38") (pintype "bidirectional"))
    )
    (net (code "117") (name "unconnected-(IC5-PC8-Pad39)") (class "Default")
      (node (ref "IC5") (pin "39") (pinfunction "PC8_39") (pintype "bidirectional"))
    )
    (net (code "118") (name "unconnected-(IC5-PC9{slash}I2S2_CKIN{slash}I2S3_CKIN-Pad40)") (class "Default")
      (node (ref "IC5") (pin "40") (pinfunction "PC9/I2S2_CKIN/I2S3_CKIN_40") (pintype "bidirectional"))
    )
    (net (code "119") (name "unconnected-(IC5-PC12{slash}UART5_TX{slash}I2S3_SD{slash}USART3_CK-Pad53)") (class "Default")
      (node (ref "IC5") (pin "53") (pinfunction "PC12/UART5_TX/I2S3_SD/USART3_CK_53") (pintype "bidirectional"))
    )
    (net (code "120") (name "unconnected-(IC5-PC13-TAMPER-RTC-Pad2)") (class "Default")
      (node (ref "IC5") (pin "2") (pinfunction "PC13-TAMPER-RTC_2") (pintype "bidirectional"))
    )
    (net (code "121") (name "unconnected-(IC5-PC14{slash}OSC32_IN-Pad3)") (class "Default")
      (node (ref "IC5") (pin "3") (pinfunction "PC14/OSC32_IN_3") (pintype "bidirectional"))
    )
    (net (code "122") (name "unconnected-(IC5-PC15{slash}OSC_OUT-Pad4)") (class "Default")
      (node (ref "IC5") (pin "4") (pinfunction "PC15/OSC_OUT_4") (pintype "bidirectional"))
    )
    (net (code "123") (name "unconnected-(IC5-PD2{slash}TIM3-ETR-Pad54)") (class "Default")
      (node (ref "IC5") (pin "54") (pinfunction "PD2/TIM3-ETR_54") (pintype "bidirectional"))
    )
    (net (code "124") (name "unconnected-(IC8-CLKOUT-Pad2)") (class "Default")
      (node (ref "IC8") (pin "2") (pinfunction "CLKOUT_2") (pintype "bidirectional"))
    )
    (net (code "125") (name "unconnected-(IC8-LHPOUT-Pad9)") (class "Default")
      (node (ref "IC8") (pin "9") (pinfunction "LHPOUT_9") (pintype "bidirectional"))
    )
    (net (code "126") (name "unconnected-(IC8-MICBIAS-Pad17)") (class "Default")
      (node (ref "IC8") (pin "17") (pinfunction "MICBIAS_17") (pintype "bidirectional"))
    )
    (net (code "127") (name "unconnected-(IC8-MICIN-Pad18)") (class "Default")
      (node (ref "IC8") (pin "18") (pinfunction "MICIN_18") (pintype "bidirectional"))
    )
    (net (code "128") (name "unconnected-(IC8-RHPOUT-Pad10)") (class "Default")
      (node (ref "IC8") (pin "10") (pinfunction "RHPOUT_10") (pintype "bidirectional"))
    )
    (net (code "129") (name "unconnected-(IC11-QH*-Pad9)") (class "Default")
      (node (ref "IC11") (pin "9") (pinfunction "QH*_9") (pintype "tri_state"))
    )
    (net (code "130") (name "unconnected-(J3-PadNORM)") (class "Default")
      (node (ref "J3") (pin "NORM") (pinfunction "NORM_NORM") (pintype "passive"))
    )
    (net (code "131") (name "unconnected-(J4-PadNORM)") (class "Default")
      (node (ref "J4") (pin "NORM") (pinfunction "NORM_NORM") (pintype "passive"))
    )
    (net (code "132") (name "unconnected-(J5-PadNORM)") (class "Default")
      (node (ref "J5") (pin "NORM") (pinfunction "NORM_NORM") (pintype "passive"))
    )
    (net (code "133") (name "unconnected-(J6-PadNORM)") (class "Default")
      (node (ref "J6") (pin "NORM") (pinfunction "NORM_NORM") (pintype "passive"))
    )
    (net (code "134") (name "unconnected-(J7-PadNORM)") (class "Default")
      (node (ref "J7") (pin "NORM") (pinfunction "NORM_NORM") (pintype "passive"))
    )
    (net (code "135") (name "unconnected-(J9-PadNORM)") (class "Default")
      (node (ref "J9") (pin "NORM") (pinfunction "NORM_NORM") (pintype "passive"))
    )
    (net (code "136") (name "unconnected-(J10-PadNORM)") (class "Default")
      (node (ref "J10") (pin "NORM") (pinfunction "NORM_NORM") (pintype "passive"))
    )
    (net (code "137") (name "unconnected-(J11-PadNORM)") (class "Default")
      (node (ref "J11") (pin "NORM") (pinfunction "NORM_NORM") (pintype "passive"))
    )
    (net (code "138") (name "unconnected-(J12-PadNORM)") (class "Default")
      (node (ref "J12") (pin "NORM") (pinfunction "NORM_NORM") (pintype "passive"))
    )
    (net (code "139") (name "unconnected-(JP2-Pad7)") (class "Default")
      (node (ref "JP2") (pin "7") (pinfunction "7_7") (pintype "passive"))
    )
  )
)
